# senseBox-MCU_v13.net
KiCad netlist of a schematic drawn in EAGLE
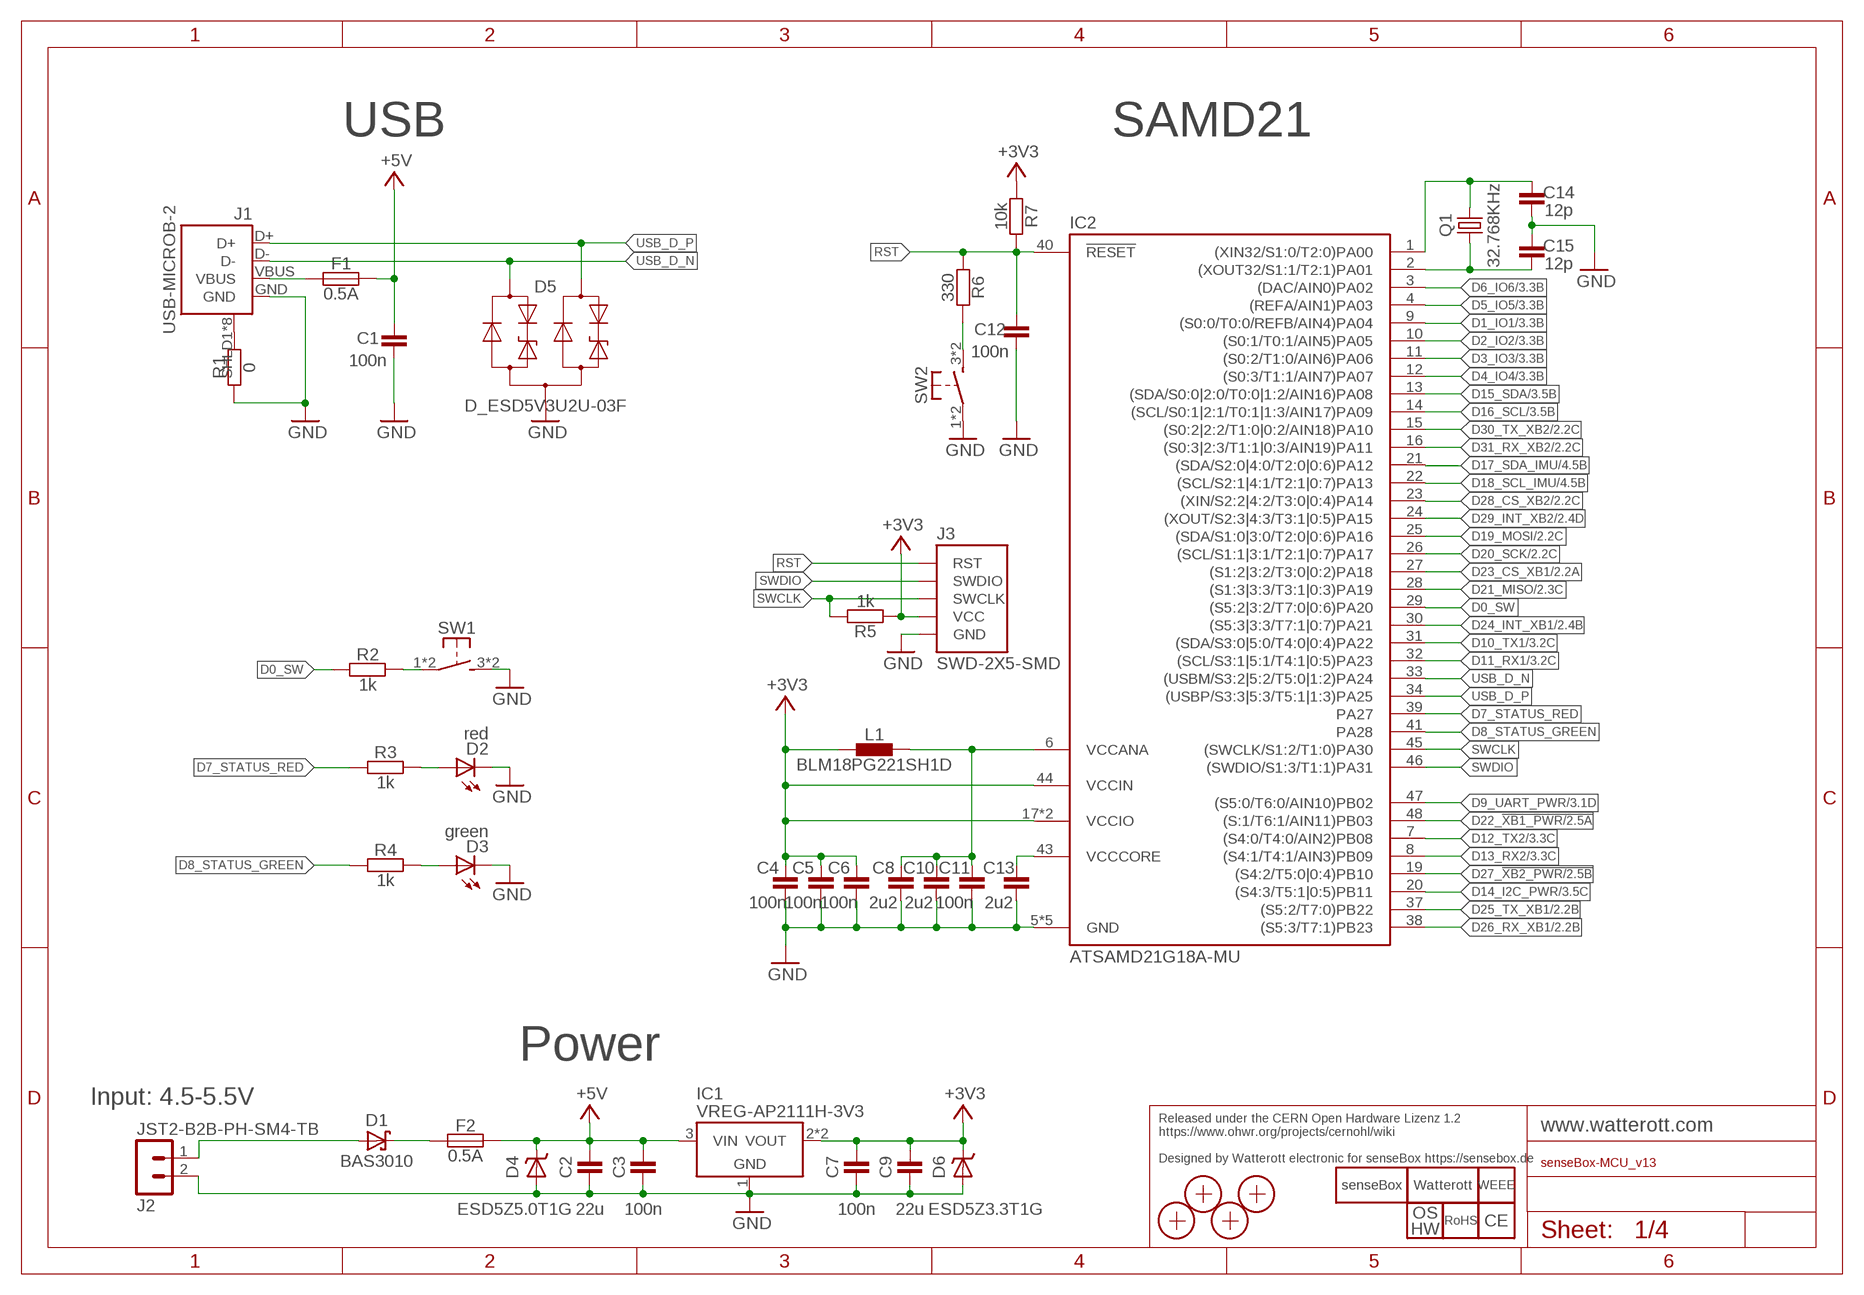
[diagram p0: schematic, sheet 1]
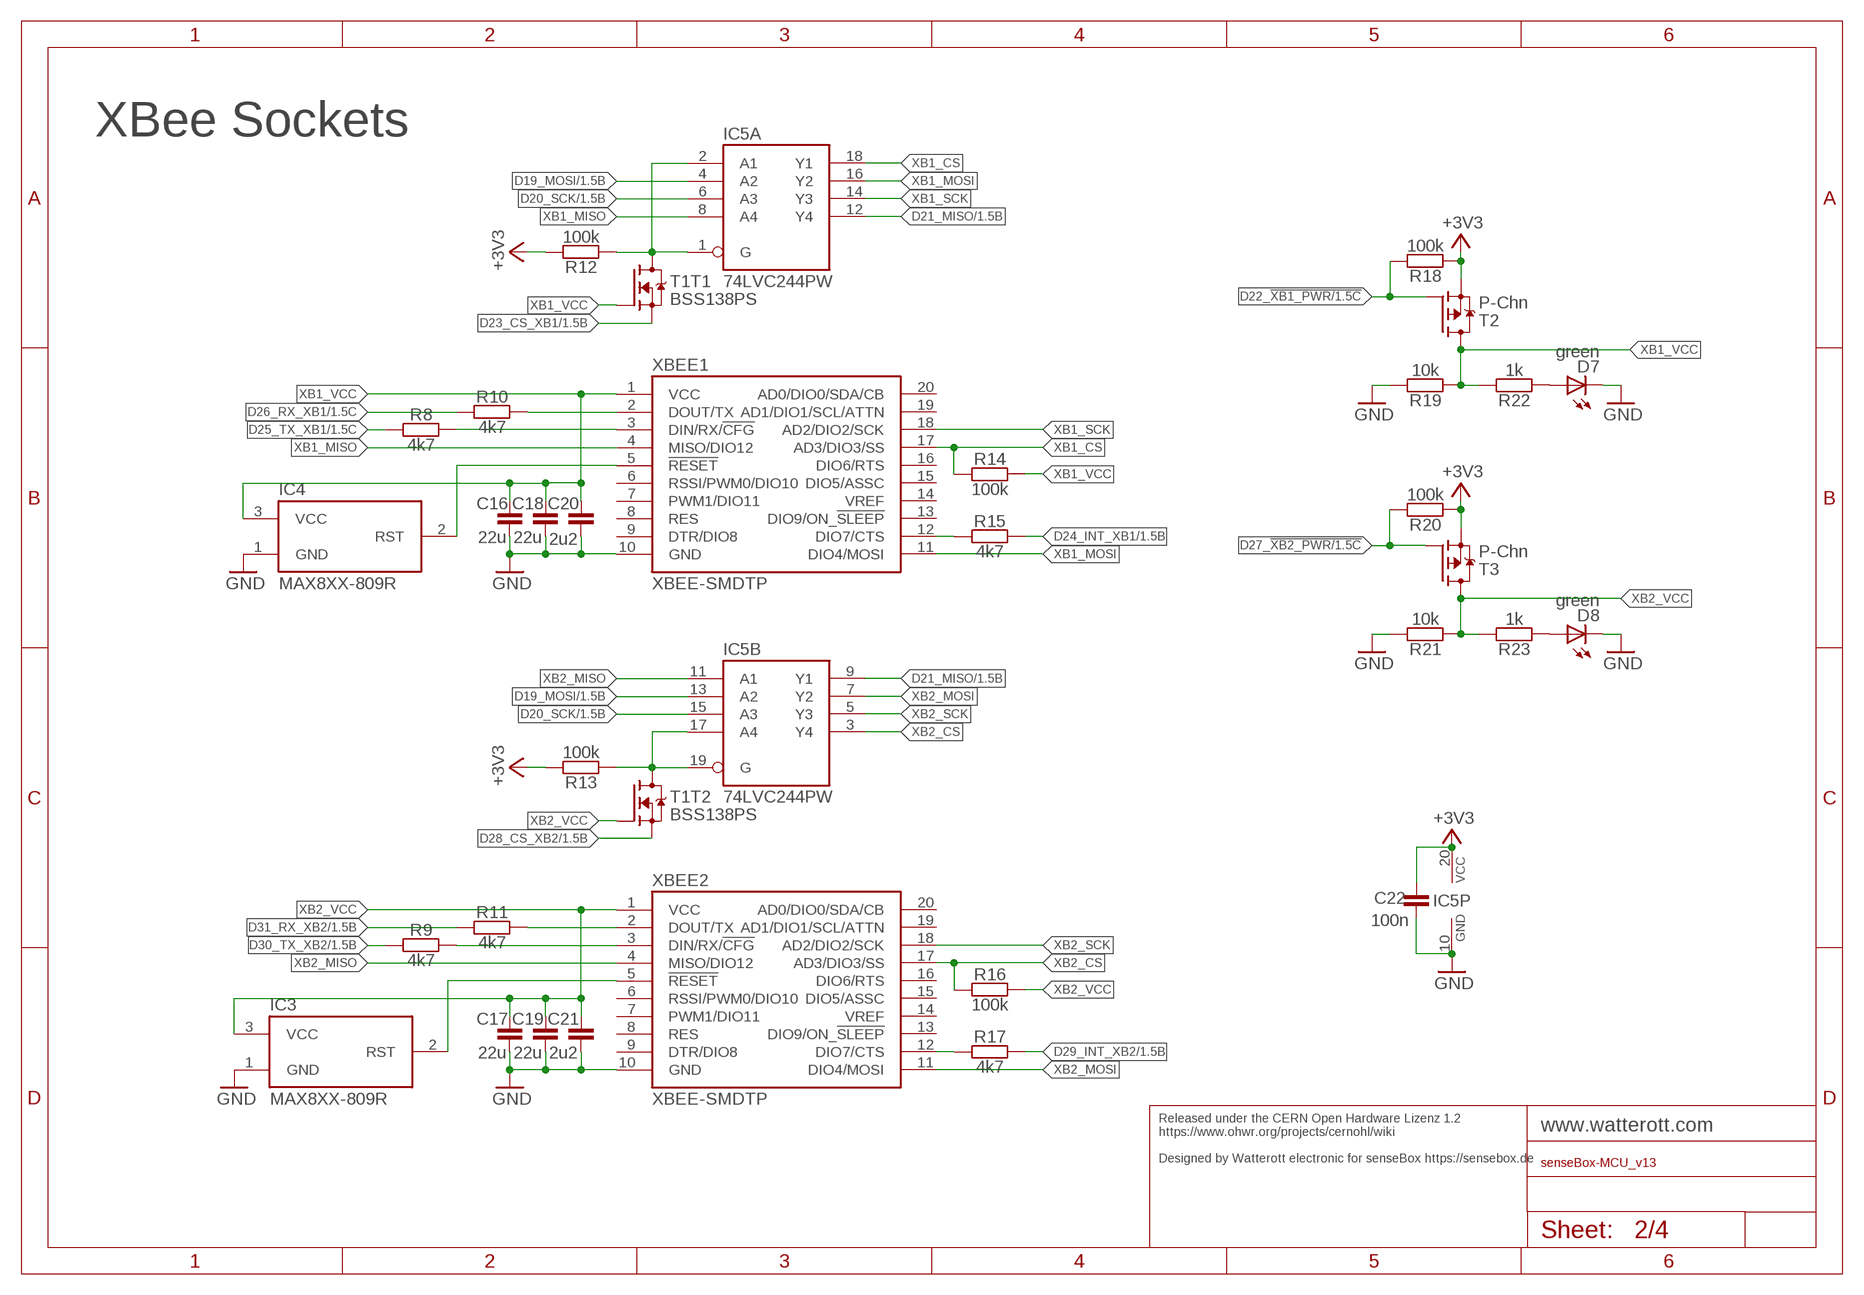
[diagram p1: schematic, sheet 2]
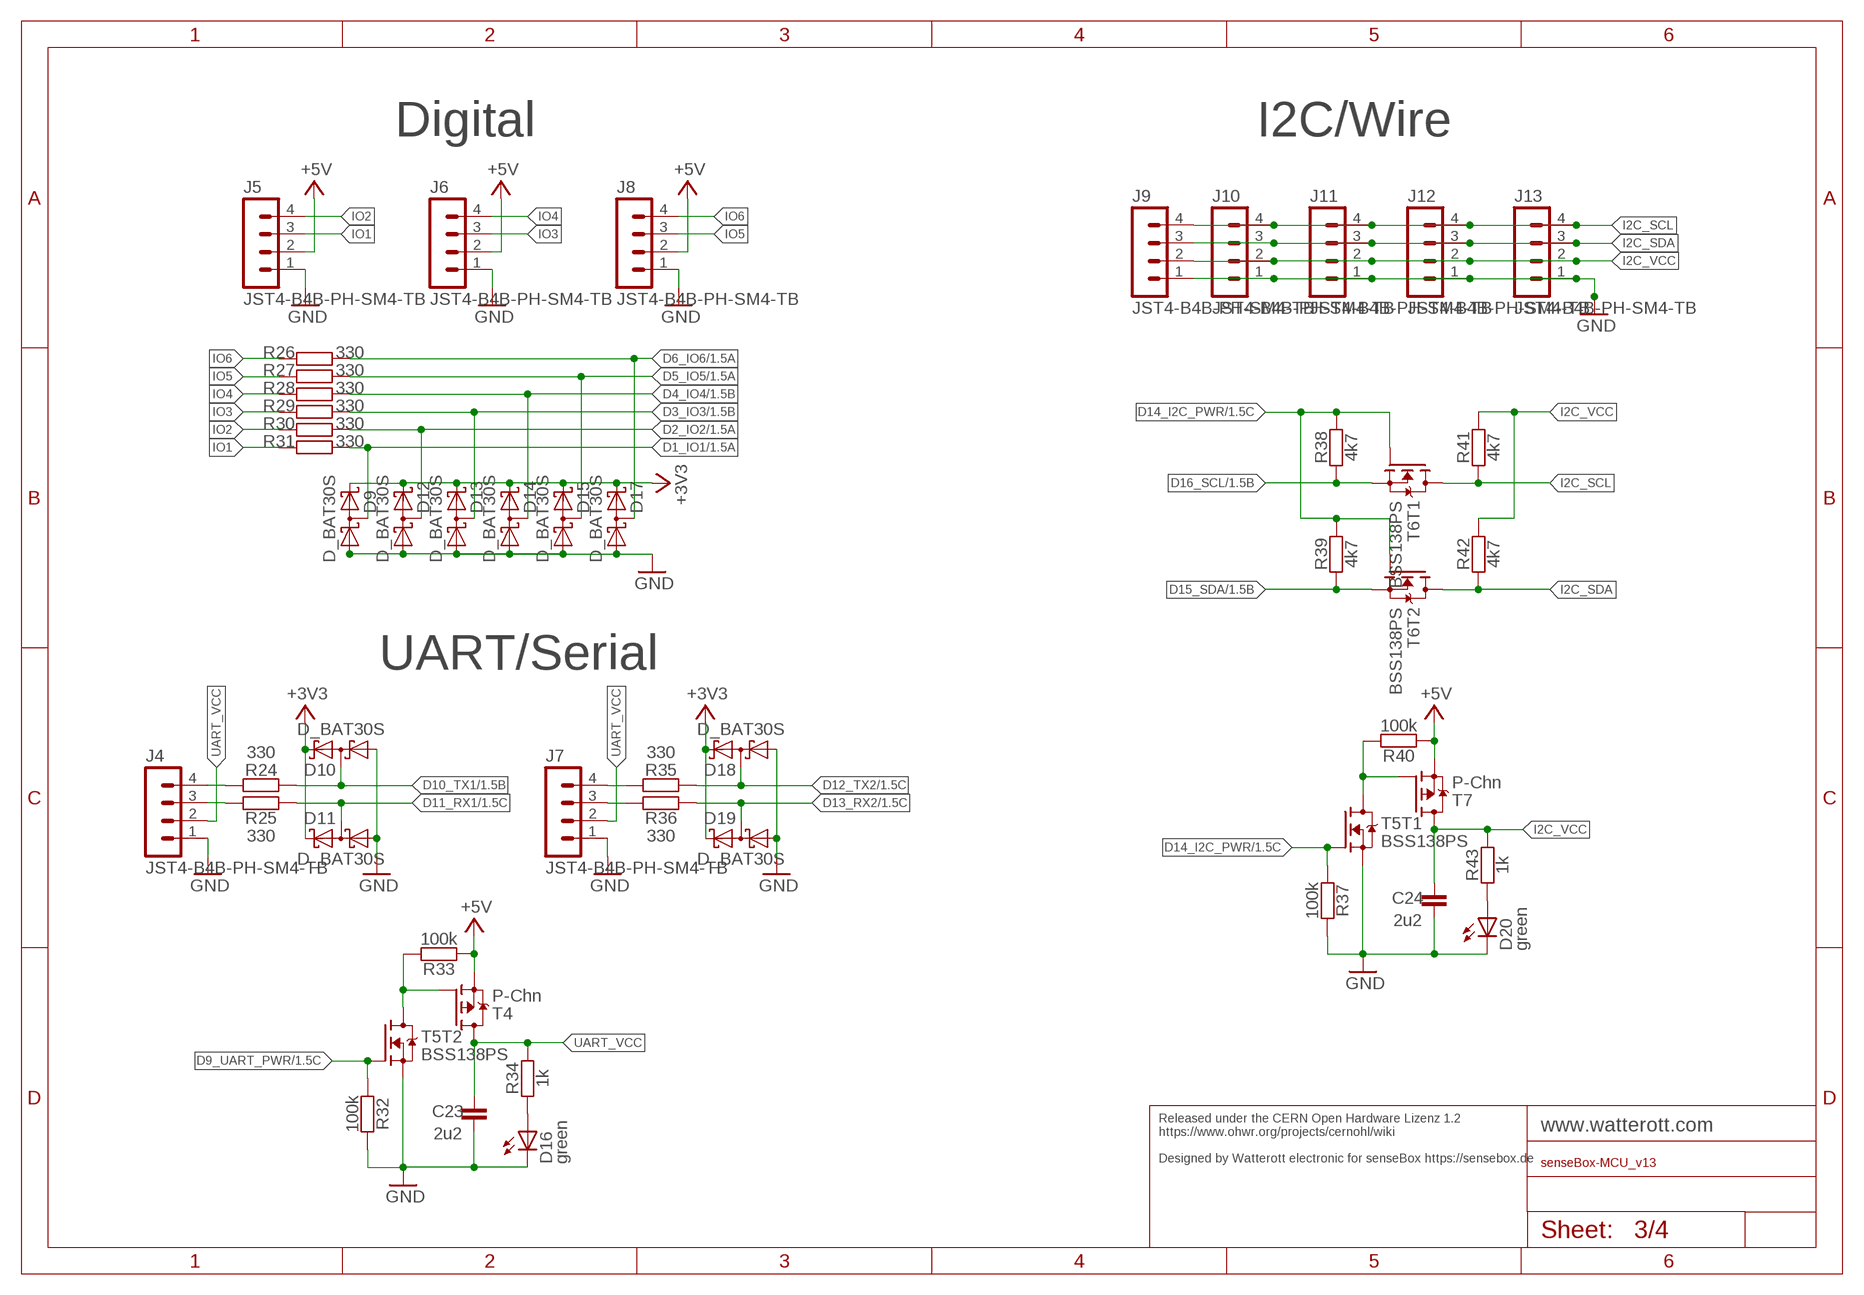
[diagram p2: schematic, sheet 3]
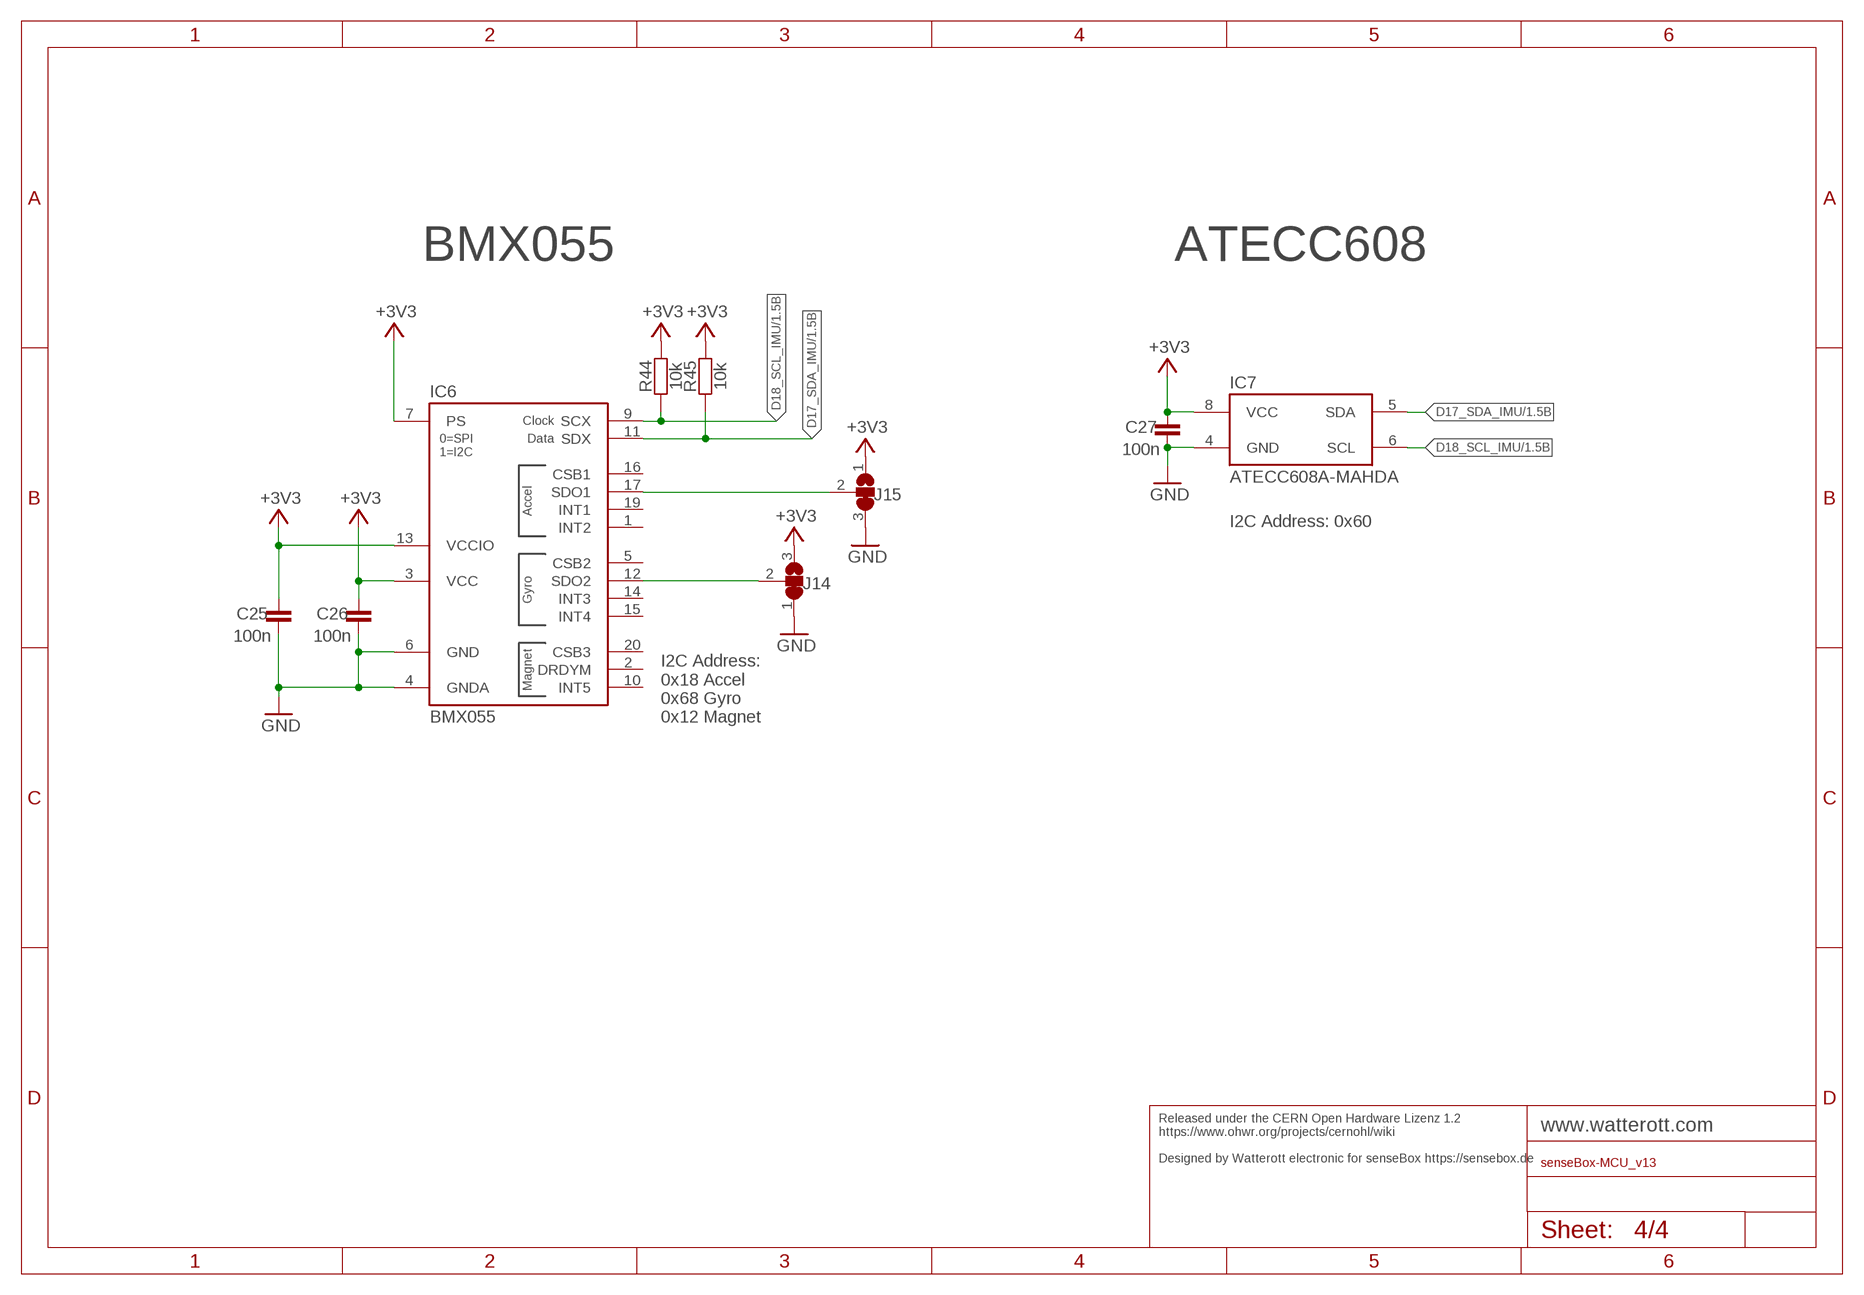
[diagram p3: schematic, sheet 4]

(export (version "E")
  (design (tool "Eeschema 10.0.6"))
  (components
    (comp (ref "C25")
      (value "100n")
      (footprint "eagle-import:C0402")
      (libsource (lib "eagle-import") (part "CAPACITOR-0402"))
    )
    (comp (ref "C26")
      (value "100n")
      (footprint "eagle-import:C0402")
      (libsource (lib "eagle-import") (part "CAPACITOR-0402"))
    )
    (comp (ref "C27")
      (value "100n")
      (footprint "eagle-import:C0402")
      (libsource (lib "eagle-import") (part "CAPACITOR-0402"))
    )
    (comp (ref "IC6")
      (value "BMX055")
      (footprint "eagle-import:BMX055")
      (libsource (lib "eagle-import") (part "BMX055"))
    )
    (comp (ref "IC7")
      (value "ATECC608A-MAHDA")
      (footprint "eagle-import:UDFN8")
      (libsource (lib "eagle-import") (part "ATECC608A-MAHDA"))
    )
    (comp (ref "J14")
      (value "JUMPER3-0402")
      (footprint "eagle-import:JUMPER3-0402")
      (libsource (lib "eagle-import") (part "JUMPER3-0402"))
    )
    (comp (ref "J15")
      (value "JUMPER3-0402")
      (footprint "eagle-import:JUMPER3-0402")
      (libsource (lib "eagle-import") (part "JUMPER3-0402"))
    )
    (comp (ref "R44")
      (value "10k")
      (footprint "eagle-import:C0402")
      (libsource (lib "eagle-import") (part "RESISTOR-0402"))
    )
    (comp (ref "R45")
      (value "10k")
      (footprint "eagle-import:C0402")
      (libsource (lib "eagle-import") (part "RESISTOR-0402"))
    )
    (comp (ref "C23")
      (value "2u2")
      (footprint "eagle-import:C0402")
      (libsource (lib "eagle-import") (part "CAPACITOR-0402"))
    )
    (comp (ref "C24")
      (value "2u2")
      (footprint "eagle-import:C0402")
      (libsource (lib "eagle-import") (part "CAPACITOR-0402"))
    )
    (comp (ref "D9")
      (value "D_BAT30S")
      (footprint "eagle-import:SOT323")
      (libsource (lib "eagle-import") (part "D_BAT30S"))
    )
    (comp (ref "D10")
      (value "D_BAT30S")
      (footprint "eagle-import:SOT323")
      (libsource (lib "eagle-import") (part "D_BAT30S"))
    )
    (comp (ref "D11")
      (value "D_BAT30S")
      (footprint "eagle-import:SOT323")
      (libsource (lib "eagle-import") (part "D_BAT30S"))
    )
    (comp (ref "D12")
      (value "D_BAT30S")
      (footprint "eagle-import:SOT323")
      (libsource (lib "eagle-import") (part "D_BAT30S"))
    )
    (comp (ref "D13")
      (value "D_BAT30S")
      (footprint "eagle-import:SOT323")
      (libsource (lib "eagle-import") (part "D_BAT30S"))
    )
    (comp (ref "D14")
      (value "D_BAT30S")
      (footprint "eagle-import:SOT323")
      (libsource (lib "eagle-import") (part "D_BAT30S"))
    )
    (comp (ref "D15")
      (value "D_BAT30S")
      (footprint "eagle-import:SOT323")
      (libsource (lib "eagle-import") (part "D_BAT30S"))
    )
    (comp (ref "D16")
      (value "green")
      (footprint "eagle-import:C0603")
      (libsource (lib "eagle-import") (part "LED-0603"))
    )
    (comp (ref "D17")
      (value "D_BAT30S")
      (footprint "eagle-import:SOT323")
      (libsource (lib "eagle-import") (part "D_BAT30S"))
    )
    (comp (ref "D18")
      (value "D_BAT30S")
      (footprint "eagle-import:SOT323")
      (libsource (lib "eagle-import") (part "D_BAT30S"))
    )
    (comp (ref "D19")
      (value "D_BAT30S")
      (footprint "eagle-import:SOT323")
      (libsource (lib "eagle-import") (part "D_BAT30S"))
    )
    (comp (ref "D20")
      (value "green")
      (footprint "eagle-import:C0603")
      (libsource (lib "eagle-import") (part "LED-0603"))
    )
    (comp (ref "J4")
      (value "JST4-B4B-PH-SM4-TB")
      (footprint "eagle-import:JST_B4B-PH-SM4-TB")
      (libsource (lib "eagle-import") (part "JST4-B4B-PH-SM4-TB"))
    )
    (comp (ref "J5")
      (value "JST4-B4B-PH-SM4-TB")
      (footprint "eagle-import:JST_B4B-PH-SM4-TB")
      (libsource (lib "eagle-import") (part "JST4-B4B-PH-SM4-TB"))
    )
    (comp (ref "J6")
      (value "JST4-B4B-PH-SM4-TB")
      (footprint "eagle-import:JST_B4B-PH-SM4-TB")
      (libsource (lib "eagle-import") (part "JST4-B4B-PH-SM4-TB"))
    )
    (comp (ref "J7")
      (value "JST4-B4B-PH-SM4-TB")
      (footprint "eagle-import:JST_B4B-PH-SM4-TB")
      (libsource (lib "eagle-import") (part "JST4-B4B-PH-SM4-TB"))
    )
    (comp (ref "J8")
      (value "JST4-B4B-PH-SM4-TB")
      (footprint "eagle-import:JST_B4B-PH-SM4-TB")
      (libsource (lib "eagle-import") (part "JST4-B4B-PH-SM4-TB"))
    )
    (comp (ref "J9")
      (value "JST4-B4B-PH-SM4-TB")
      (footprint "eagle-import:JST_B4B-PH-SM4-TB")
      (libsource (lib "eagle-import") (part "JST4-B4B-PH-SM4-TB"))
    )
    (comp (ref "J10")
      (value "JST4-B4B-PH-SM4-TB")
      (footprint "eagle-import:JST_B4B-PH-SM4-TB")
      (libsource (lib "eagle-import") (part "JST4-B4B-PH-SM4-TB"))
    )
    (comp (ref "J11")
      (value "JST4-B4B-PH-SM4-TB")
      (footprint "eagle-import:JST_B4B-PH-SM4-TB")
      (libsource (lib "eagle-import") (part "JST4-B4B-PH-SM4-TB"))
    )
    (comp (ref "J12")
      (value "JST4-B4B-PH-SM4-TB")
      (footprint "eagle-import:JST_B4B-PH-SM4-TB")
      (libsource (lib "eagle-import") (part "JST4-B4B-PH-SM4-TB"))
    )
    (comp (ref "J13")
      (value "JST4-B4B-PH-SM4-TB")
      (footprint "eagle-import:JST_B4B-PH-SM4-TB")
      (libsource (lib "eagle-import") (part "JST4-B4B-PH-SM4-TB"))
    )
    (comp (ref "R24")
      (value "330")
      (footprint "eagle-import:C0402")
      (libsource (lib "eagle-import") (part "RESISTOR-0402"))
    )
    (comp (ref "R25")
      (value "330")
      (footprint "eagle-import:C0402")
      (libsource (lib "eagle-import") (part "RESISTOR-0402"))
    )
    (comp (ref "R26")
      (value "330")
      (footprint "eagle-import:C0402")
      (libsource (lib "eagle-import") (part "RESISTOR-0402"))
    )
    (comp (ref "R27")
      (value "330")
      (footprint "eagle-import:C0402")
      (libsource (lib "eagle-import") (part "RESISTOR-0402"))
    )
    (comp (ref "R28")
      (value "330")
      (footprint "eagle-import:C0402")
      (libsource (lib "eagle-import") (part "RESISTOR-0402"))
    )
    (comp (ref "R29")
      (value "330")
      (footprint "eagle-import:C0402")
      (libsource (lib "eagle-import") (part "RESISTOR-0402"))
    )
    (comp (ref "R30")
      (value "330")
      (footprint "eagle-import:C0402")
      (libsource (lib "eagle-import") (part "RESISTOR-0402"))
    )
    (comp (ref "R31")
      (value "330")
      (footprint "eagle-import:C0402")
      (libsource (lib "eagle-import") (part "RESISTOR-0402"))
    )
    (comp (ref "R32")
      (value "100k")
      (footprint "eagle-import:C0402")
      (libsource (lib "eagle-import") (part "RESISTOR-0402"))
    )
    (comp (ref "R33")
      (value "100k")
      (footprint "eagle-import:C0402")
      (libsource (lib "eagle-import") (part "RESISTOR-0402"))
    )
    (comp (ref "R34")
      (value "1k")
      (footprint "eagle-import:C0402")
      (libsource (lib "eagle-import") (part "RESISTOR-0402"))
    )
    (comp (ref "R35")
      (value "330")
      (footprint "eagle-import:C0402")
      (libsource (lib "eagle-import") (part "RESISTOR-0402"))
    )
    (comp (ref "R36")
      (value "330")
      (footprint "eagle-import:C0402")
      (libsource (lib "eagle-import") (part "RESISTOR-0402"))
    )
    (comp (ref "R37")
      (value "100k")
      (footprint "eagle-import:C0402")
      (libsource (lib "eagle-import") (part "RESISTOR-0402"))
    )
    (comp (ref "R38")
      (value "4k7")
      (footprint "eagle-import:C0402")
      (libsource (lib "eagle-import") (part "RESISTOR-0402"))
    )
    (comp (ref "R39")
      (value "4k7")
      (footprint "eagle-import:C0402")
      (libsource (lib "eagle-import") (part "RESISTOR-0402"))
    )
    (comp (ref "R40")
      (value "100k")
      (footprint "eagle-import:C0402")
      (libsource (lib "eagle-import") (part "RESISTOR-0402"))
    )
    (comp (ref "R41")
      (value "4k7")
      (footprint "eagle-import:C0402")
      (libsource (lib "eagle-import") (part "RESISTOR-0402"))
    )
    (comp (ref "R42")
      (value "4k7")
      (footprint "eagle-import:C0402")
      (libsource (lib "eagle-import") (part "RESISTOR-0402"))
    )
    (comp (ref "R43")
      (value "1k")
      (footprint "eagle-import:C0402")
      (libsource (lib "eagle-import") (part "RESISTOR-0402"))
    )
    (comp (ref "T4")
      (value "P-Chn")
      (footprint "eagle-import:SOT23")
      (libsource (lib "eagle-import") (part "MOSFET-P-SOT23"))
    )
    (comp (ref "T5")
      (value "BSS138PS")
      (footprint "eagle-import:SOT363")
      (libsource (lib "eagle-import") (part "BSS138PS"))
    )
    (comp (ref "T6")
      (value "BSS138PS")
      (footprint "eagle-import:SOT363")
      (libsource (lib "eagle-import") (part "BSS138PS"))
    )
    (comp (ref "T7")
      (value "P-Chn")
      (footprint "eagle-import:SOT23")
      (libsource (lib "eagle-import") (part "MOSFET-P-SOT23"))
    )
    (comp (ref "C1")
      (value "100n")
      (footprint "eagle-import:C0402")
      (libsource (lib "eagle-import") (part "CAPACITOR-0402"))
    )
    (comp (ref "C2")
      (value "22u")
      (footprint "eagle-import:C0805")
      (libsource (lib "eagle-import") (part "CAPACITOR-0805"))
    )
    (comp (ref "C3")
      (value "100n")
      (footprint "eagle-import:C0402")
      (libsource (lib "eagle-import") (part "CAPACITOR-0402"))
    )
    (comp (ref "C4")
      (value "100n")
      (footprint "eagle-import:C0402")
      (libsource (lib "eagle-import") (part "CAPACITOR-0402"))
    )
    (comp (ref "C5")
      (value "100n")
      (footprint "eagle-import:C0402")
      (libsource (lib "eagle-import") (part "CAPACITOR-0402"))
    )
    (comp (ref "C6")
      (value "100n")
      (footprint "eagle-import:C0402")
      (libsource (lib "eagle-import") (part "CAPACITOR-0402"))
    )
    (comp (ref "C7")
      (value "100n")
      (footprint "eagle-import:C0402")
      (libsource (lib "eagle-import") (part "CAPACITOR-0402"))
    )
    (comp (ref "C8")
      (value "2u2")
      (footprint "eagle-import:C0402")
      (libsource (lib "eagle-import") (part "CAPACITOR-0402"))
    )
    (comp (ref "C9")
      (value "22u")
      (footprint "eagle-import:C0805")
      (libsource (lib "eagle-import") (part "CAPACITOR-0805"))
    )
    (comp (ref "C10")
      (value "2u2")
      (footprint "eagle-import:C0402")
      (libsource (lib "eagle-import") (part "CAPACITOR-0402"))
    )
    (comp (ref "C11")
      (value "100n")
      (footprint "eagle-import:C0402")
      (libsource (lib "eagle-import") (part "CAPACITOR-0402"))
    )
    (comp (ref "C12")
      (value "100n")
      (footprint "eagle-import:C0402")
      (libsource (lib "eagle-import") (part "CAPACITOR-0402"))
    )
    (comp (ref "C13")
      (value "2u2")
      (footprint "eagle-import:C0402")
      (libsource (lib "eagle-import") (part "CAPACITOR-0402"))
    )
    (comp (ref "C14")
      (value "12p")
      (footprint "eagle-import:C0402")
      (libsource (lib "eagle-import") (part "CAPACITOR-0402"))
    )
    (comp (ref "C15")
      (value "12p")
      (footprint "eagle-import:C0402")
      (libsource (lib "eagle-import") (part "CAPACITOR-0402"))
    )
    (comp (ref "D1")
      (value "BAS3010")
      (footprint "eagle-import:SOD323")
      (libsource (lib "eagle-import") (part "D_SCHOTTKY-SOD323"))
    )
    (comp (ref "D2")
      (value "red")
      (footprint "eagle-import:C0603")
      (libsource (lib "eagle-import") (part "LED-0603"))
    )
    (comp (ref "D3")
      (value "green")
      (footprint "eagle-import:C0603")
      (libsource (lib "eagle-import") (part "LED-0603"))
    )
    (comp (ref "D4")
      (value "ESD5Z5.0T1G")
      (footprint "eagle-import:SOD523")
      (libsource (lib "eagle-import") (part "D_TVS-SOD523"))
    )
    (comp (ref "D5")
      (value "D_ESD5V3U2U-03F")
      (footprint "eagle-import:SOT723")
      (libsource (lib "eagle-import") (part "D_ESD5V3U2U-03F"))
    )
    (comp (ref "D6")
      (value "ESD5Z3.3T1G")
      (footprint "eagle-import:SOD523")
      (libsource (lib "eagle-import") (part "D_TVS-SOD523"))
    )
    (comp (ref "F1")
      (value "0.5A")
      (footprint "eagle-import:C0805")
      (libsource (lib "eagle-import") (part "FUSE-0805"))
    )
    (comp (ref "F2")
      (value "0.5A")
      (footprint "eagle-import:C0805")
      (libsource (lib "eagle-import") (part "FUSE-0805"))
    )
    (comp (ref "IC1")
      (value "VREG-AP2111H-3V3")
      (footprint "eagle-import:SOT223")
      (libsource (lib "eagle-import") (part "VREG-TS1117CW-3V3"))
    )
    (comp (ref "IC2")
      (value "ATSAMD21G18A-MU")
      (footprint "eagle-import:QFN48-PAD")
      (libsource (lib "eagle-import") (part "ATSAMD21G18A-MU"))
    )
    (comp (ref "J1")
      (value "USB-MICROB-2")
      (footprint "eagle-import:USB-MICROB-10118194")
      (libsource (lib "eagle-import") (part "USB-MICROB-2"))
    )
    (comp (ref "J2")
      (value "JST2-B2B-PH-SM4-TB")
      (footprint "eagle-import:JST_B2B-PH-SM4-TB")
      (libsource (lib "eagle-import") (part "JST2-B2B-PH-SM4-TB"))
    )
    (comp (ref "J3")
      (value "SWD-2X5-SMD")
      (footprint "eagle-import:SWD-2X5_SMD")
      (libsource (lib "eagle-import") (part "SWD-2X5-SMD"))
    )
    (comp (ref "L1")
      (value "BLM18PG221SH1D")
      (footprint "eagle-import:C0603")
      (libsource (lib "eagle-import") (part "INDUCTOR-0603"))
    )
    (comp (ref "LOGO1")
      (value "LOGO_SENSEBOX-12")
      (footprint "eagle-import:SB_12MM")
      (libsource (lib "eagle-import") (part "LOGO_SENSEBOX-12"))
    )
    (comp (ref "LOGO3")
      (value "OSHW_LOGOX0070")
      (footprint "eagle-import:OSHW_3MM")
      (libsource (lib "eagle-import") (part "LOGO_OSHW-3"))
    )
    (comp (ref "LOGO4")
      (value "LOGO_SPARK-4")
      (footprint "eagle-import:SPARK_4MM")
      (libsource (lib "eagle-import") (part "LOGO_SPARK-4"))
    )
    (comp (ref "LOGO5")
      (value "LOGO_ROHS-4")
      (footprint "eagle-import:ROHS_4MM")
      (libsource (lib "eagle-import") (part "LOGO_ROHS-4"))
    )
    (comp (ref "LOGO6")
      (value "LOGO_WEEE-4")
      (footprint "eagle-import:WEEE_4MM")
      (libsource (lib "eagle-import") (part "LOGO_WEEE-4"))
    )
    (comp (ref "LOGO7")
      (value "LOGO_CE-4")
      (footprint "eagle-import:CE_4MM")
      (libsource (lib "eagle-import") (part "LOGO_CE-4"))
    )
    (comp (ref "Q1")
      (value "32.768KHz")
      (footprint "eagle-import:CRYSTAL_ZM315")
      (libsource (lib "eagle-import") (part "CRYSTAL-ZM315"))
    )
    (comp (ref "R1")
      (value "0")
      (footprint "eagle-import:C0402")
      (libsource (lib "eagle-import") (part "RESISTOR-0402"))
    )
    (comp (ref "R2")
      (value "1k")
      (footprint "eagle-import:C0402")
      (libsource (lib "eagle-import") (part "RESISTOR-0402"))
    )
    (comp (ref "R3")
      (value "1k")
      (footprint "eagle-import:C0402")
      (libsource (lib "eagle-import") (part "RESISTOR-0402"))
    )
    (comp (ref "R4")
      (value "1k")
      (footprint "eagle-import:C0402")
      (libsource (lib "eagle-import") (part "RESISTOR-0402"))
    )
    (comp (ref "R5")
      (value "1k")
      (footprint "eagle-import:C0402")
      (libsource (lib "eagle-import") (part "RESISTOR-0402"))
    )
    (comp (ref "R6")
      (value "330")
      (footprint "eagle-import:C0402")
      (libsource (lib "eagle-import") (part "RESISTOR-0402"))
    )
    (comp (ref "R7")
      (value "10k")
      (footprint "eagle-import:C0402")
      (libsource (lib "eagle-import") (part "RESISTOR-0402"))
    )
    (comp (ref "SW1")
      (value "PTS645SH50SMTR92-Grey")
      (footprint "eagle-import:SW6X6_SMD")
      (libsource (lib "eagle-import") (part "SW-TACTILE-6X6_SMD"))
    )
    (comp (ref "SW2")
      (value "PTS645SK50SMTR92-Red")
      (footprint "eagle-import:SW6X6_SMD")
      (libsource (lib "eagle-import") (part "SW-TACTILE-6X6_SMD"))
    )
    (comp (ref "X1")
      (value "PASSER-07")
      (footprint "eagle-import:PASSER_07MM")
      (libsource (lib "eagle-import") (part "PASSER-07"))
    )
    (comp (ref "X2")
      (value "PASSER-07")
      (footprint "eagle-import:PASSER_07MM")
      (libsource (lib "eagle-import") (part "PASSER-07"))
    )
    (comp (ref "X3")
      (value "PASSER-07")
      (footprint "eagle-import:PASSER_07MM")
      (libsource (lib "eagle-import") (part "PASSER-07"))
    )
    (comp (ref "X4")
      (value "PASSER-07")
      (footprint "eagle-import:PASSER_07MM")
      (libsource (lib "eagle-import") (part "PASSER-07"))
    )
    (comp (ref "C16")
      (value "22u")
      (footprint "eagle-import:C0805")
      (libsource (lib "eagle-import") (part "CAPACITOR-0805"))
    )
    (comp (ref "C17")
      (value "22u")
      (footprint "eagle-import:C0805")
      (libsource (lib "eagle-import") (part "CAPACITOR-0805"))
    )
    (comp (ref "C18")
      (value "22u")
      (footprint "eagle-import:C0805")
      (libsource (lib "eagle-import") (part "CAPACITOR-0805"))
    )
    (comp (ref "C19")
      (value "22u")
      (footprint "eagle-import:C0805")
      (libsource (lib "eagle-import") (part "CAPACITOR-0805"))
    )
    (comp (ref "C20")
      (value "2u2")
      (footprint "eagle-import:C0402")
      (libsource (lib "eagle-import") (part "CAPACITOR-0402"))
    )
    (comp (ref "C21")
      (value "2u2")
      (footprint "eagle-import:C0402")
      (libsource (lib "eagle-import") (part "CAPACITOR-0402"))
    )
    (comp (ref "C22")
      (value "100n")
      (footprint "eagle-import:C0402")
      (libsource (lib "eagle-import") (part "CAPACITOR-0402"))
    )
    (comp (ref "D7")
      (value "green")
      (footprint "eagle-import:C0603")
      (libsource (lib "eagle-import") (part "LED-0603"))
    )
    (comp (ref "D8")
      (value "green")
      (footprint "eagle-import:C0603")
      (libsource (lib "eagle-import") (part "LED-0603"))
    )
    (comp (ref "IC3")
      (value "MAX8XX-809R")
      (footprint "eagle-import:SOT23")
      (libsource (lib "eagle-import") (part "MAX8XX-809R"))
    )
    (comp (ref "IC4")
      (value "MAX8XX-809R")
      (footprint "eagle-import:SOT23")
      (libsource (lib "eagle-import") (part "MAX8XX-809R"))
    )
    (comp (ref "IC5")
      (value "74LVC244PW")
      (footprint "eagle-import:TSSOP20")
      (libsource (lib "eagle-import") (part "74244PWLVC"))
    )
    (comp (ref "R8")
      (value "4k7")
      (footprint "eagle-import:C0402")
      (libsource (lib "eagle-import") (part "RESISTOR-0402"))
    )
    (comp (ref "R9")
      (value "4k7")
      (footprint "eagle-import:C0402")
      (libsource (lib "eagle-import") (part "RESISTOR-0402"))
    )
    (comp (ref "R10")
      (value "4k7")
      (footprint "eagle-import:C0402")
      (libsource (lib "eagle-import") (part "RESISTOR-0402"))
    )
    (comp (ref "R11")
      (value "4k7")
      (footprint "eagle-import:C0402")
      (libsource (lib "eagle-import") (part "RESISTOR-0402"))
    )
    (comp (ref "R12")
      (value "100k")
      (footprint "eagle-import:C0402")
      (libsource (lib "eagle-import") (part "RESISTOR-0402"))
    )
    (comp (ref "R13")
      (value "100k")
      (footprint "eagle-import:C0402")
      (libsource (lib "eagle-import") (part "RESISTOR-0402"))
    )
    (comp (ref "R14")
      (value "100k")
      (footprint "eagle-import:C0402")
      (libsource (lib "eagle-import") (part "RESISTOR-0402"))
    )
    (comp (ref "R15")
      (value "4k7")
      (footprint "eagle-import:C0402")
      (libsource (lib "eagle-import") (part "RESISTOR-0402"))
    )
    (comp (ref "R16")
      (value "100k")
      (footprint "eagle-import:C0402")
      (libsource (lib "eagle-import") (part "RESISTOR-0402"))
    )
    (comp (ref "R17")
      (value "4k7")
      (footprint "eagle-import:C0402")
      (libsource (lib "eagle-import") (part "RESISTOR-0402"))
    )
    (comp (ref "R18")
      (value "100k")
      (footprint "eagle-import:C0402")
      (libsource (lib "eagle-import") (part "RESISTOR-0402"))
    )
    (comp (ref "R19")
      (value "10k")
      (footprint "eagle-import:C0402")
      (libsource (lib "eagle-import") (part "RESISTOR-0402"))
    )
    (comp (ref "R20")
      (value "100k")
      (footprint "eagle-import:C0402")
      (libsource (lib "eagle-import") (part "RESISTOR-0402"))
    )
    (comp (ref "R21")
      (value "10k")
      (footprint "eagle-import:C0402")
      (libsource (lib "eagle-import") (part "RESISTOR-0402"))
    )
    (comp (ref "R22")
      (value "1k")
      (footprint "eagle-import:C0402")
      (libsource (lib "eagle-import") (part "RESISTOR-0402"))
    )
    (comp (ref "R23")
      (value "1k")
      (footprint "eagle-import:C0402")
      (libsource (lib "eagle-import") (part "RESISTOR-0402"))
    )
    (comp (ref "T1")
      (value "BSS138PS")
      (footprint "eagle-import:SOT363")
      (libsource (lib "eagle-import") (part "BSS138PS"))
    )
    (comp (ref "T2")
      (value "P-Chn")
      (footprint "eagle-import:SOT23")
      (libsource (lib "eagle-import") (part "MOSFET-P-SOT23"))
    )
    (comp (ref "T3")
      (value "P-Chn")
      (footprint "eagle-import:SOT23")
      (libsource (lib "eagle-import") (part "MOSFET-P-SOT23"))
    )
    (comp (ref "XBEE1")
      (value "XBEE-SMDTP")
      (footprint "eagle-import:XBEE_SMD_TP")
      (libsource (lib "eagle-import") (part "XBEE-SMDTP"))
    )
    (comp (ref "XBEE2")
      (value "XBEE-SMDTP")
      (footprint "eagle-import:XBEE_SMD_TP")
      (libsource (lib "eagle-import") (part "XBEE-SMDTP"))
    )
  )
  (nets
    (net (code "1") (name "+3V3") (class "Default")
      (node (ref "C22") (pin "2") (pinfunction "2_2") (pintype "passive"))
      (node (ref "C25") (pin "2") (pinfunction "2_2") (pintype "passive"))
      (node (ref "C26") (pin "2") (pinfunction "2_2") (pintype "passive"))
      (node (ref "C27") (pin "2") (pinfunction "2_2") (pintype "passive"))
      (node (ref "C4") (pin "2") (pinfunction "2_2") (pintype "passive"))
      (node (ref "C5") (pin "2") (pinfunction "2_2") (pintype "passive"))
      (node (ref "C6") (pin "2") (pinfunction "2_2") (pintype "passive"))
      (node (ref "C7") (pin "2") (pinfunction "2_2") (pintype "passive"))
      (node (ref "C9") (pin "2") (pinfunction "2_2") (pintype "passive"))
      (node (ref "D10") (pin "2") (pinfunction "C_2") (pintype "passive"))
      (node (ref "D11") (pin "2") (pinfunction "C_2") (pintype "passive"))
      (node (ref "D12") (pin "2") (pinfunction "C_2") (pintype "passive"))
      (node (ref "D13") (pin "2") (pinfunction "C_2") (pintype "passive"))
      (node (ref "D14") (pin "2") (pinfunction "C_2") (pintype "passive"))
      (node (ref "D15") (pin "2") (pinfunction "C_2") (pintype "passive"))
      (node (ref "D17") (pin "2") (pinfunction "C_2") (pintype "passive"))
      (node (ref "D18") (pin "2") (pinfunction "C_2") (pintype "passive"))
      (node (ref "D19") (pin "2") (pinfunction "C_2") (pintype "passive"))
      (node (ref "D6") (pin "C") (pinfunction "C_C") (pintype "passive"))
      (node (ref "D9") (pin "2") (pinfunction "C_2") (pintype "passive"))
      (node (ref "IC1") (pin "2") (pinfunction "VOUT_2") (pintype "power_in"))
      (node (ref "IC1") (pin "4") (pinfunction "VOUT_4") (pintype "power_in"))
      (node (ref "IC2") (pin "17") (pinfunction "VCCIO_17") (pintype "power_in"))
      (node (ref "IC2") (pin "36") (pinfunction "VCCIO_36") (pintype "power_in"))
      (node (ref "IC2") (pin "44") (pinfunction "VCCIN_44") (pintype "power_in"))
      (node (ref "IC5") (pin "20") (pinfunction "VCC_20") (pintype "power_in"))
      (node (ref "IC6") (pin "13") (pinfunction "VCCIO_13") (pintype "power_in"))
      (node (ref "IC6") (pin "3") (pinfunction "VCC_3") (pintype "power_in"))
      (node (ref "IC6") (pin "7") (pinfunction "PS_7") (pintype "input"))
      (node (ref "IC7") (pin "8") (pinfunction "VCC_8") (pintype "power_in"))
      (node (ref "J14") (pin "3") (pinfunction "3_3") (pintype "passive"))
      (node (ref "J15") (pin "1") (pinfunction "1_1") (pintype "passive"))
      (node (ref "J3") (pin "VCC") (pinfunction "VCC_VCC") (pintype "power_in"))
      (node (ref "L1") (pin "1") (pinfunction "1_1") (pintype "passive"))
      (node (ref "R12") (pin "2") (pinfunction "2_2") (pintype "passive"))
      (node (ref "R13") (pin "2") (pinfunction "2_2") (pintype "passive"))
      (node (ref "R18") (pin "1") (pinfunction "1_1") (pintype "passive"))
      (node (ref "R20") (pin "1") (pinfunction "1_1") (pintype "passive"))
      (node (ref "R44") (pin "2") (pinfunction "2_2") (pintype "passive"))
      (node (ref "R45") (pin "2") (pinfunction "2_2") (pintype "passive"))
      (node (ref "R5") (pin "1") (pinfunction "1_1") (pintype "passive"))
      (node (ref "R7") (pin "1") (pinfunction "1_1") (pintype "passive"))
      (node (ref "T2") (pin "2") (pinfunction "S_2") (pintype "passive"))
      (node (ref "T3") (pin "2") (pinfunction "S_2") (pintype "passive"))
    )
    (net (code "2") (name "+5V") (class "Default")
      (node (ref "C1") (pin "2") (pinfunction "2_2") (pintype "passive"))
      (node (ref "C2") (pin "2") (pinfunction "2_2") (pintype "passive"))
      (node (ref "C3") (pin "2") (pinfunction "2_2") (pintype "passive"))
      (node (ref "D4") (pin "C") (pinfunction "C_C") (pintype "passive"))
      (node (ref "F1") (pin "2") (pinfunction "2_2") (pintype "passive"))
      (node (ref "F2") (pin "2") (pinfunction "2_2") (pintype "passive"))
      (node (ref "IC1") (pin "3") (pinfunction "VIN_3") (pintype "power_in"))
      (node (ref "J5") (pin "2") (pinfunction "2_2") (pintype "passive"))
      (node (ref "J6") (pin "2") (pinfunction "2_2") (pintype "passive"))
      (node (ref "J8") (pin "2") (pinfunction "2_2") (pintype "passive"))
      (node (ref "R33") (pin "1") (pinfunction "1_1") (pintype "passive"))
      (node (ref "R40") (pin "1") (pinfunction "1_1") (pintype "passive"))
      (node (ref "T4") (pin "2") (pinfunction "S_2") (pintype "passive"))
      (node (ref "T7") (pin "2") (pinfunction "S_2") (pintype "passive"))
    )
    (net (code "3") (name "D0_SW") (class "Default")
      (node (ref "IC2") (pin "29") (pinfunction "(S5:2|3:2/T7:0|0:6)PA20_29") (pintype "bidirectional"))
      (node (ref "R2") (pin "1") (pinfunction "1_1") (pintype "passive"))
    )
    (net (code "4") (name "D1_IO1") (class "Default")
      (node (ref "D9") (pin "3") (pinfunction "CA_3") (pintype "passive"))
      (node (ref "IC2") (pin "9") (pinfunction "(S0:0/T0:0/REFB/AIN4)PA04_9") (pintype "bidirectional"))
      (node (ref "R31") (pin "1") (pinfunction "1_1") (pintype "passive"))
    )
    (net (code "5") (name "D2_IO2") (class "Default")
      (node (ref "D12") (pin "3") (pinfunction "CA_3") (pintype "passive"))
      (node (ref "IC2") (pin "10") (pinfunction "(S0:1/T0:1/AIN5)PA05_10") (pintype "bidirectional"))
      (node (ref "R30") (pin "1") (pinfunction "1_1") (pintype "passive"))
    )
    (net (code "6") (name "D3_IO3") (class "Default")
      (node (ref "D13") (pin "3") (pinfunction "CA_3") (pintype "passive"))
      (node (ref "IC2") (pin "11") (pinfunction "(S0:2/T1:0/AIN6)PA06_11") (pintype "bidirectional"))
      (node (ref "R29") (pin "1") (pinfunction "1_1") (pintype "passive"))
    )
    (net (code "7") (name "D4_IO4") (class "Default")
      (node (ref "D14") (pin "3") (pinfunction "CA_3") (pintype "passive"))
      (node (ref "IC2") (pin "12") (pinfunction "(S0:3/T1:1/AIN7)PA07_12") (pintype "bidirectional"))
      (node (ref "R28") (pin "1") (pinfunction "1_1") (pintype "passive"))
    )
    (net (code "8") (name "D5_IO5") (class "Default")
      (node (ref "D15") (pin "3") (pinfunction "CA_3") (pintype "passive"))
      (node (ref "IC2") (pin "4") (pinfunction "(REFA/AIN1)PA03_4") (pintype "bidirectional"))
      (node (ref "R27") (pin "1") (pinfunction "1_1") (pintype "passive"))
    )
    (net (code "9") (name "D6_IO6") (class "Default")
      (node (ref "D17") (pin "3") (pinfunction "CA_3") (pintype "passive"))
      (node (ref "IC2") (pin "3") (pinfunction "(DAC/AIN0)PA02_3") (pintype "bidirectional"))
      (node (ref "R26") (pin "1") (pinfunction "1_1") (pintype "passive"))
    )
    (net (code "10") (name "D7_STATUS_RED") (class "Default")
      (node (ref "IC2") (pin "39") (pinfunction "PA27_39") (pintype "bidirectional"))
      (node (ref "R3") (pin "1") (pinfunction "1_1") (pintype "passive"))
    )
    (net (code "11") (name "D8_STATUS_GREEN") (class "Default")
      (node (ref "IC2") (pin "41") (pinfunction "PA28_41") (pintype "bidirectional"))
      (node (ref "R4") (pin "1") (pinfunction "1_1") (pintype "passive"))
    )
    (net (code "12") (name "D9_UART_PWR") (class "Default")
      (node (ref "IC2") (pin "47") (pinfunction "(S5:0/T6:0/AIN10)PB02_47") (pintype "bidirectional"))
      (node (ref "R32") (pin "1") (pinfunction "1_1") (pintype "passive"))
      (node (ref "T5") (pin "5") (pinfunction "G_5") (pintype "passive"))
    )
    (net (code "13") (name "D10_TX1") (class "Default")
      (node (ref "D10") (pin "3") (pinfunction "CA_3") (pintype "passive"))
      (node (ref "IC2") (pin "31") (pinfunction "(SDA/S3:0|5:0/T4:0|0:4)PA22_31") (pintype "bidirectional"))
      (node (ref "R24") (pin "1") (pinfunction "1_1") (pintype "passive"))
    )
    (net (code "14") (name "D11_RX1") (class "Default")
      (node (ref "D11") (pin "3") (pinfunction "CA_3") (pintype "passive"))
      (node (ref "IC2") (pin "32") (pinfunction "(SCL/S3:1|5:1/T4:1|0:5)PA23_32") (pintype "bidirectional"))
      (node (ref "R25") (pin "1") (pinfunction "1_1") (pintype "passive"))
    )
    (net (code "15") (name "D12_TX2") (class "Default")
      (node (ref "D18") (pin "3") (pinfunction "CA_3") (pintype "passive"))
      (node (ref "IC2") (pin "7") (pinfunction "(S4:0/T4:0/AIN2)PB08_7") (pintype "bidirectional"))
      (node (ref "R35") (pin "1") (pinfunction "1_1") (pintype "passive"))
    )
    (net (code "16") (name "D13_RX2") (class "Default")
      (node (ref "D19") (pin "3") (pinfunction "CA_3") (pintype "passive"))
      (node (ref "IC2") (pin "8") (pinfunction "(S4:1/T4:1/AIN3)PB09_8") (pintype "bidirectional"))
      (node (ref "R36") (pin "1") (pinfunction "1_1") (pintype "passive"))
    )
    (net (code "17") (name "D14_I2C_PWR") (class "Default")
      (node (ref "IC2") (pin "20") (pinfunction "(S4:3/T5:1|0:5)PB11_20") (pintype "bidirectional"))
      (node (ref "R37") (pin "1") (pinfunction "1_1") (pintype "passive"))
      (node (ref "R38") (pin "2") (pinfunction "2_2") (pintype "passive"))
      (node (ref "R39") (pin "2") (pinfunction "2_2") (pintype "passive"))
      (node (ref "T5") (pin "2") (pinfunction "G_2") (pintype "passive"))
      (node (ref "T6") (pin "2") (pinfunction "G_2") (pintype "passive"))
      (node (ref "T6") (pin "5") (pinfunction "G_5") (pintype "passive"))
    )
    (net (code "18") (name "D15_SDA") (class "Default")
      (node (ref "IC2") (pin "13") (pinfunction "(SDA/S0:0|2:0/T0:0|1:2/AIN16)PA08_13") (pintype "bidirectional"))
      (node (ref "R39") (pin "1") (pinfunction "1_1") (pintype "passive"))
      (node (ref "T6") (pin "4") (pinfunction "S_4") (pintype "passive"))
    )
    (net (code "19") (name "D16_SCL") (class "Default")
      (node (ref "IC2") (pin "14") (pinfunction "(SCL/S0:1|2:1/T0:1|1:3/AIN17)PA09_14") (pintype "bidirectional"))
      (node (ref "R38") (pin "1") (pinfunction "1_1") (pintype "passive"))
      (node (ref "T6") (pin "1") (pinfunction "S_1") (pintype "passive"))
    )
    (net (code "20") (name "D17_SDA_IMU") (class "Default")
      (node (ref "IC2") (pin "21") (pinfunction "(SDA/S2:0|4:0/T2:0|0:6)PA12_21") (pintype "bidirectional"))
      (node (ref "IC6") (pin "11") (pinfunction "SDX_11") (pintype "bidirectional"))
      (node (ref "IC7") (pin "5") (pinfunction "SDA_5") (pintype "bidirectional"))
      (node (ref "R45") (pin "1") (pinfunction "1_1") (pintype "passive"))
    )
    (net (code "21") (name "D18_SCL_IMU") (class "Default")
      (node (ref "IC2") (pin "22") (pinfunction "(SCL/S2:1|4:1/T2:1|0:7)PA13_22") (pintype "bidirectional"))
      (node (ref "IC6") (pin "9") (pinfunction "SCX_9") (pintype "bidirectional"))
      (node (ref "IC7") (pin "6") (pinfunction "SCL_6") (pintype "bidirectional"))
      (node (ref "R44") (pin "1") (pinfunction "1_1") (pintype "passive"))
    )
    (net (code "22") (name "D19_MOSI") (class "Default")
      (node (ref "IC2") (pin "25") (pinfunction "(SDA/S1:0|3:0/T2:0|0:6)PA16_25") (pintype "bidirectional"))
      (node (ref "IC5") (pin "13") (pinfunction "A2_13") (pintype "input"))
      (node (ref "IC5") (pin "4") (pinfunction "A2_4") (pintype "input"))
    )
    (net (code "23") (name "D20_SCK") (class "Default")
      (node (ref "IC2") (pin "26") (pinfunction "(SCL/S1:1|3:1/T2:1|0:7)PA17_26") (pintype "bidirectional"))
      (node (ref "IC5") (pin "15") (pinfunction "A3_15") (pintype "input"))
      (node (ref "IC5") (pin "6") (pinfunction "A3_6") (pintype "input"))
    )
    (net (code "24") (name "D21_MISO") (class "Default")
      (node (ref "IC2") (pin "28") (pinfunction "(S1:3|3:3/T3:1|0:3)PA19_28") (pintype "bidirectional"))
      (node (ref "IC5") (pin "12") (pinfunction "Y4_12") (pintype "tri_state"))
      (node (ref "IC5") (pin "9") (pinfunction "Y1_9") (pintype "tri_state"))
    )
    (net (code "25") (name "D22_~{XB1_PWR}") (class "Default")
      (node (ref "IC2") (pin "48") (pinfunction "(S:1/T6:1/AIN11)PB03_48") (pintype "bidirectional"))
      (node (ref "R18") (pin "2") (pinfunction "2_2") (pintype "passive"))
      (node (ref "T2") (pin "1") (pinfunction "G_1") (pintype "passive"))
    )
    (net (code "26") (name "D23_CS_XB1") (class "Default")
      (node (ref "IC2") (pin "27") (pinfunction "(S1:2|3:2/T3:0|0:2)PA18_27") (pintype "bidirectional"))
      (node (ref "T1") (pin "1") (pinfunction "S_1") (pintype "passive"))
    )
    (net (code "27") (name "D24_INT_XB1") (class "Default")
      (node (ref "IC2") (pin "30") (pinfunction "(S5:3|3:3/T7:1|0:7)PA21_30") (pintype "bidirectional"))
      (node (ref "R15") (pin "2") (pinfunction "2_2") (pintype "passive"))
    )
    (net (code "28") (name "D25_TX_XB1") (class "Default")
      (node (ref "IC2") (pin "37") (pinfunction "(S5:2/T7:0)PB22_37") (pintype "bidirectional"))
      (node (ref "R8") (pin "1") (pinfunction "1_1") (pintype "passive"))
    )
    (net (code "29") (name "D26_RX_XB1") (class "Default")
      (node (ref "IC2") (pin "38") (pinfunction "(S5:3/T7:1)PB23_38") (pintype "bidirectional"))
      (node (ref "R10") (pin "1") (pinfunction "1_1") (pintype "passive"))
    )
    (net (code "30") (name "D27_~{XB2_PWR}") (class "Default")
      (node (ref "IC2") (pin "19") (pinfunction "(S4:2/T5:0|0:4)PB10_19") (pintype "bidirectional"))
      (node (ref "R20") (pin "2") (pinfunction "2_2") (pintype "passive"))
      (node (ref "T3") (pin "1") (pinfunction "G_1") (pintype "passive"))
    )
    (net (code "31") (name "D28_CS_XB2") (class "Default")
      (node (ref "IC2") (pin "23") (pinfunction "(XIN/S2:2|4:2/T3:0|0:4)PA14_23") (pintype "bidirectional"))
      (node (ref "T1") (pin "4") (pinfunction "S_4") (pintype "passive"))
    )
    (net (code "32") (name "D29_INT_XB2") (class "Default")
      (node (ref "IC2") (pin "24") (pinfunction "(XOUT/S2:3|4:3/T3:1|0:5)PA15_24") (pintype "bidirectional"))
      (node (ref "R17") (pin "2") (pinfunction "2_2") (pintype "passive"))
    )
    (net (code "33") (name "D30_TX_XB2") (class "Default")
      (node (ref "IC2") (pin "15") (pinfunction "(S0:2|2:2/T1:0|0:2/AIN18)PA10_15") (pintype "bidirectional"))
      (node (ref "R9") (pin "1") (pinfunction "1_1") (pintype "passive"))
    )
    (net (code "34") (name "D31_RX_XB2") (class "Default")
      (node (ref "IC2") (pin "16") (pinfunction "(S0:3|2:3/T1:1|0:3/AIN19)PA11_16") (pintype "bidirectional"))
      (node (ref "R11") (pin "1") (pinfunction "1_1") (pintype "passive"))
    )
    (net (code "35") (name "GND") (class "Default")
      (node (ref "C1") (pin "1") (pinfunction "1_1") (pintype "passive"))
      (node (ref "C10") (pin "1") (pinfunction "1_1") (pintype "passive"))
      (node (ref "C11") (pin "1") (pinfunction "1_1") (pintype "passive"))
      (node (ref "C12") (pin "1") (pinfunction "1_1") (pintype "passive"))
      (node (ref "C13") (pin "1") (pinfunction "1_1") (pintype "passive"))
      (node (ref "C14") (pin "2") (pinfunction "2_2") (pintype "passive"))
      (node (ref "C15") (pin "1") (pinfunction "1_1") (pintype "passive"))
      (node (ref "C16") (pin "1") (pinfunction "1_1") (pintype "passive"))
      (node (ref "C17") (pin "1") (pinfunction "1_1") (pintype "passive"))
      (node (ref "C18") (pin "1") (pinfunction "1_1") (pintype "passive"))
      (node (ref "C19") (pin "1") (pinfunction "1_1") (pintype "passive"))
      (node (ref "C2") (pin "1") (pinfunction "1_1") (pintype "passive"))
      (node (ref "C20") (pin "1") (pinfunction "1_1") (pintype "passive"))
      (node (ref "C21") (pin "1") (pinfunction "1_1") (pintype "passive"))
      (node (ref "C22") (pin "1") (pinfunction "1_1") (pintype "passive"))
      (node (ref "C23") (pin "1") (pinfunction "1_1") (pintype "passive"))
      (node (ref "C24") (pin "1") (pinfunction "1_1") (pintype "passive"))
      (node (ref "C25") (pin "1") (pinfunction "1_1") (pintype "passive"))
      (node (ref "C26") (pin "1") (pinfunction "1_1") (pintype "passive"))
      (node (ref "C27") (pin "1") (pinfunction "1_1") (pintype "passive"))
      (node (ref "C3") (pin "1") (pinfunction "1_1") (pintype "passive"))
      (node (ref "C4") (pin "1") (pinfunction "1_1") (pintype "passive"))
      (node (ref "C5") (pin "1") (pinfunction "1_1") (pintype "passive"))
      (node (ref "C6") (pin "1") (pinfunction "1_1") (pintype "passive"))
      (node (ref "C7") (pin "1") (pinfunction "1_1") (pintype "passive"))
      (node (ref "C8") (pin "1") (pinfunction "1_1") (pintype "passive"))
      (node (ref "C9") (pin "1") (pinfunction "1_1") (pintype "passive"))
      (node (ref "D10") (pin "1") (pinfunction "A_1") (pintype "passive"))
      (node (ref "D11") (pin "1") (pinfunction "A_1") (pintype "passive"))
      (node (ref "D12") (pin "1") (pinfunction "A_1") (pintype "passive"))
      (node (ref "D13") (pin "1") (pinfunction "A_1") (pintype "passive"))
      (node (ref "D14") (pin "1") (pinfunction "A_1") (pintype "passive"))
      (node (ref "D15") (pin "1") (pinfunction "A_1") (pintype "passive"))
      (node (ref "D16") (pin "C") (pinfunction "C_C") (pintype "passive"))
      (node (ref "D17") (pin "1") (pinfunction "A_1") (pintype "passive"))
      (node (ref "D18") (pin "1") (pinfunction "A_1") (pintype "passive"))
      (node (ref "D19") (pin "1") (pinfunction "A_1") (pintype "passive"))
      (node (ref "D2") (pin "C") (pinfunction "C_C") (pintype "passive"))
      (node (ref "D20") (pin "C") (pinfunction "C_C") (pintype "passive"))
      (node (ref "D3") (pin "C") (pinfunction "C_C") (pintype "passive"))
      (node (ref "D4") (pin "A") (pinfunction "A_A") (pintype "passive"))
      (node (ref "D5") (pin "3") (pinfunction "A_3") (pintype "passive"))
      (node (ref "D6") (pin "A") (pinfunction "A_A") (pintype "passive"))
      (node (ref "D7") (pin "C") (pinfunction "C_C") (pintype "passive"))
      (node (ref "D8") (pin "C") (pinfunction "C_C") (pintype "passive"))
      (node (ref "D9") (pin "1") (pinfunction "A_1") (pintype "passive"))
      (node (ref "IC1") (pin "1") (pinfunction "GND_1") (pintype "power_in"))
      (node (ref "IC2") (pin "18") (pinfunction "GND_18") (pintype "power_in"))
      (node (ref "IC2") (pin "35") (pinfunction "GND_35") (pintype "power_in"))
      (node (ref "IC2") (pin "42") (pinfunction "GND_42") (pintype "power_in"))
      (node (ref "IC2") (pin "5") (pinfunction "GND_5") (pintype "power_in"))
      (node (ref "IC2") (pin "TP") (pinfunction "GND_TP") (pintype "power_in"))
      (node (ref "IC3") (pin "1") (pinfunction "GND_1") (pintype "power_in"))
      (node (ref "IC4") (pin "1") (pinfunction "GND_1") (pintype "power_in"))
      (node (ref "IC5") (pin "10") (pinfunction "GND_10") (pintype "power_in"))
      (node (ref "IC6") (pin "4") (pinfunction "GNDA_4") (pintype "power_in"))
      (node (ref "IC6") (pin "6") (pinfunction "GND_6") (pintype "power_in"))
      (node (ref "IC7") (pin "4") (pinfunction "GND_4") (pintype "power_in"))
      (node (ref "J1") (pin "GND") (pinfunction "GND_GND") (pintype "power_in"))
      (node (ref "J10") (pin "1") (pinfunction "1_1") (pintype "passive"))
      (node (ref "J11") (pin "1") (pinfunction "1_1") (pintype "passive"))
      (node (ref "J12") (pin "1") (pinfunction "1_1") (pintype "passive"))
      (node (ref "J13") (pin "1") (pinfunction "1_1") (pintype "passive"))
      (node (ref "J14") (pin "1") (pinfunction "1_1") (pintype "passive"))
      (node (ref "J15") (pin "3") (pinfunction "3_3") (pintype "passive"))
      (node (ref "J2") (pin "2") (pinfunction "2_2") (pintype "passive"))
      (node (ref "J3") (pin "GND@1") (pinfunction "GND_GND@1") (pintype "power_in"))
      (node (ref "J3") (pin "GND@2") (pinfunction "GND_GND@2") (pintype "power_in"))
      (node (ref "J3") (pin "GND@3") (pinfunction "GND_GND@3") (pintype "power_in"))
      (node (ref "J4") (pin "1") (pinfunction "1_1") (pintype "passive"))
      (node (ref "J5") (pin "1") (pinfunction "1_1") (pintype "passive"))
      (node (ref "J6") (pin "1") (pinfunction "1_1") (pintype "passive"))
      (node (ref "J7") (pin "1") (pinfunction "1_1") (pintype "passive"))
      (node (ref "J8") (pin "1") (pinfunction "1_1") (pintype "passive"))
      (node (ref "J9") (pin "1") (pinfunction "1_1") (pintype "passive"))
      (node (ref "R1") (pin "1") (pinfunction "1_1") (pintype "passive"))
      (node (ref "R19") (pin "2") (pinfunction "2_2") (pintype "passive"))
      (node (ref "R21") (pin "2") (pinfunction "2_2") (pintype "passive"))
      (node (ref "R32") (pin "2") (pinfunction "2_2") (pintype "passive"))
      (node (ref "R37") (pin "2") (pinfunction "2_2") (pintype "passive"))
      (node (ref "SW1") (pin "3") (pinfunction "S1_3") (pintype "passive"))
      (node (ref "SW1") (pin "4") (pinfunction "S1_4") (pintype "passive"))
      (node (ref "SW2") (pin "1") (pinfunction "P1_1") (pintype "passive"))
      (node (ref "SW2") (pin "2") (pinfunction "P1_2") (pintype "passive"))
      (node (ref "T5") (pin "1") (pinfunction "S_1") (pintype "passive"))
      (node (ref "T5") (pin "4") (pinfunction "S_4") (pintype "passive"))
      (node (ref "XBEE1") (pin "10") (pinfunction "GND_10") (pintype "power_in"))
      (node (ref "XBEE2") (pin "10") (pinfunction "GND_10") (pintype "power_in"))
    )
    (net (code "36") (name "I2C_SCL") (class "Default")
      (node (ref "J10") (pin "4") (pinfunction "4_4") (pintype "passive"))
      (node (ref "J11") (pin "4") (pinfunction "4_4") (pintype "passive"))
      (node (ref "J12") (pin "4") (pinfunction "4_4") (pintype "passive"))
      (node (ref "J13") (pin "4") (pinfunction "4_4") (pintype "passive"))
      (node (ref "J9") (pin "4") (pinfunction "4_4") (pintype "passive"))
      (node (ref "R41") (pin "1") (pinfunction "1_1") (pintype "passive"))
      (node (ref "T6") (pin "6") (pinfunction "D_6") (pintype "passive"))
    )
    (net (code "37") (name "I2C_SDA") (class "Default")
      (node (ref "J10") (pin "3") (pinfunction "3_3") (pintype "passive"))
      (node (ref "J11") (pin "3") (pinfunction "3_3") (pintype "passive"))
      (node (ref "J12") (pin "3") (pinfunction "3_3") (pintype "passive"))
      (node (ref "J13") (pin "3") (pinfunction "3_3") (pintype "passive"))
      (node (ref "J9") (pin "3") (pinfunction "3_3") (pintype "passive"))
      (node (ref "R42") (pin "1") (pinfunction "1_1") (pintype "passive"))
      (node (ref "T6") (pin "3") (pinfunction "D_3") (pintype "passive"))
    )
    (net (code "38") (name "I2C_VCC") (class "Default")
      (node (ref "C24") (pin "2") (pinfunction "2_2") (pintype "passive"))
      (node (ref "J10") (pin "2") (pinfunction "2_2") (pintype "passive"))
      (node (ref "J11") (pin "2") (pinfunction "2_2") (pintype "passive"))
      (node (ref "J12") (pin "2") (pinfunction "2_2") (pintype "passive"))
      (node (ref "J13") (pin "2") (pinfunction "2_2") (pintype "passive"))
      (node (ref "J9") (pin "2") (pinfunction "2_2") (pintype "passive"))
      (node (ref "R41") (pin "2") (pinfunction "2_2") (pintype "passive"))
      (node (ref "R42") (pin "2") (pinfunction "2_2") (pintype "passive"))
      (node (ref "R43") (pin "2") (pinfunction "2_2") (pintype "passive"))
      (node (ref "T7") (pin "3") (pinfunction "D_3") (pintype "passive"))
    )
    (net (code "39") (name "IO1") (class "Default")
      (node (ref "J5") (pin "3") (pinfunction "3_3") (pintype "passive"))
      (node (ref "R31") (pin "2") (pinfunction "2_2") (pintype "passive"))
    )
    (net (code "40") (name "IO2") (class "Default")
      (node (ref "J5") (pin "4") (pinfunction "4_4") (pintype "passive"))
      (node (ref "R30") (pin "2") (pinfunction "2_2") (pintype "passive"))
    )
    (net (code "41") (name "IO3") (class "Default")
      (node (ref "J6") (pin "3") (pinfunction "3_3") (pintype "passive"))
      (node (ref "R29") (pin "2") (pinfunction "2_2") (pintype "passive"))
    )
    (net (code "42") (name "IO4") (class "Default")
      (node (ref "J6") (pin "4") (pinfunction "4_4") (pintype "passive"))
      (node (ref "R28") (pin "2") (pinfunction "2_2") (pintype "passive"))
    )
    (net (code "43") (name "IO5") (class "Default")
      (node (ref "J8") (pin "3") (pinfunction "3_3") (pintype "passive"))
      (node (ref "R27") (pin "2") (pinfunction "2_2") (pintype "passive"))
    )
    (net (code "44") (name "IO6") (class "Default")
      (node (ref "J8") (pin "4") (pinfunction "4_4") (pintype "passive"))
      (node (ref "R26") (pin "2") (pinfunction "2_2") (pintype "passive"))
    )
    (net (code "45") (name "Net-(D1-PadA)") (class "Default")
      (node (ref "D1") (pin "A") (pinfunction "A_A") (pintype "passive"))
      (node (ref "J2") (pin "1") (pinfunction "1_1") (pintype "passive"))
    )
    (net (code "46") (name "Net-(D1-PadC)") (class "Default")
      (node (ref "D1") (pin "C") (pinfunction "C_C") (pintype "passive"))
      (node (ref "F2") (pin "1") (pinfunction "1_1") (pintype "passive"))
    )
    (net (code "47") (name "Net-(D2-PadA)") (class "Default")
      (node (ref "D2") (pin "A") (pinfunction "A_A") (pintype "passive"))
      (node (ref "R3") (pin "2") (pinfunction "2_2") (pintype "passive"))
    )
    (net (code "48") (name "Net-(D3-PadA)") (class "Default")
      (node (ref "D3") (pin "A") (pinfunction "A_A") (pintype "passive"))
      (node (ref "R4") (pin "2") (pinfunction "2_2") (pintype "passive"))
    )
    (net (code "49") (name "Net-(D7-PadA)") (class "Default")
      (node (ref "D7") (pin "A") (pinfunction "A_A") (pintype "passive"))
      (node (ref "R22") (pin "1") (pinfunction "1_1") (pintype "passive"))
    )
    (net (code "50") (name "Net-(D8-PadA)") (class "Default")
      (node (ref "D8") (pin "A") (pinfunction "A_A") (pintype "passive"))
      (node (ref "R23") (pin "1") (pinfunction "1_1") (pintype "passive"))
    )
    (net (code "51") (name "Net-(D16-PadA)") (class "Default")
      (node (ref "D16") (pin "A") (pinfunction "A_A") (pintype "passive"))
      (node (ref "R34") (pin "1") (pinfunction "1_1") (pintype "passive"))
    )
    (net (code "52") (name "Net-(D20-PadA)") (class "Default")
      (node (ref "D20") (pin "A") (pinfunction "A_A") (pintype "passive"))
      (node (ref "R43") (pin "1") (pinfunction "1_1") (pintype "passive"))
    )
    (net (code "53") (name "Net-(F1-Pad1)") (class "Default")
      (node (ref "F1") (pin "1") (pinfunction "1_1") (pintype "passive"))
      (node (ref "J1") (pin "VBUS") (pinfunction "VBUS_VBUS") (pintype "power_in"))
    )
    (net (code "54") (name "Net-(IC2-(XIN32{slash}S1:0{slash}T2:0)PA00)") (class "Default")
      (node (ref "C14") (pin "1") (pinfunction "1_1") (pintype "passive"))
      (node (ref "IC2") (pin "1") (pinfunction "(XIN32/S1:0/T2:0)PA00_1") (pintype "bidirectional"))
      (node (ref "Q1") (pin "2") (pinfunction "2_2") (pintype "passive"))
    )
    (net (code "55") (name "Net-(IC2-(XOUT32{slash}S1:1{slash}T2:1)PA01)") (class "Default")
      (node (ref "C15") (pin "2") (pinfunction "2_2") (pintype "passive"))
      (node (ref "IC2") (pin "2") (pinfunction "(XOUT32/S1:1/T2:1)PA01_2") (pintype "bidirectional"))
      (node (ref "Q1") (pin "1") (pinfunction "1_1") (pintype "passive"))
    )
    (net (code "56") (name "Net-(IC2-VCCANA)") (class "Default")
      (node (ref "C10") (pin "2") (pinfunction "2_2") (pintype "passive"))
      (node (ref "C11") (pin "2") (pinfunction "2_2") (pintype "passive"))
      (node (ref "C8") (pin "2") (pinfunction "2_2") (pintype "passive"))
      (node (ref "IC2") (pin "6") (pinfunction "VCCANA_6") (pintype "power_in"))
      (node (ref "L1") (pin "2") (pinfunction "2_2") (pintype "passive"))
    )
    (net (code "57") (name "Net-(IC2-VCCCORE)") (class "Default")
      (node (ref "C13") (pin "2") (pinfunction "2_2") (pintype "passive"))
      (node (ref "IC2") (pin "43") (pinfunction "VCCCORE_43") (pintype "power_in"))
    )
    (net (code "58") (name "Net-(IC3-RST)") (class "Default")
      (node (ref "IC3") (pin "2") (pinfunction "RST_2") (pintype "output"))
      (node (ref "XBEE2") (pin "5") (pinfunction "~{RESET}_5") (pintype "bidirectional"))
    )
    (net (code "59") (name "Net-(IC4-RST)") (class "Default")
      (node (ref "IC4") (pin "2") (pinfunction "RST_2") (pintype "output"))
      (node (ref "XBEE1") (pin "5") (pinfunction "~{RESET}_5") (pintype "bidirectional"))
    )
    (net (code "60") (name "Net-(IC5A-A1)") (class "Default")
      (node (ref "IC5") (pin "1") (pinfunction "G_1") (pintype "input"))
      (node (ref "IC5") (pin "2") (pinfunction "A1_2") (pintype "input"))
      (node (ref "R12") (pin "1") (pinfunction "1_1") (pintype "passive"))
      (node (ref "T1") (pin "6") (pinfunction "D_6") (pintype "passive"))
    )
    (net (code "61") (name "Net-(IC5B-A4)") (class "Default")
      (node (ref "IC5") (pin "17") (pinfunction "A4_17") (pintype "input"))
      (node (ref "IC5") (pin "19") (pinfunction "G_19") (pintype "input"))
      (node (ref "R13") (pin "1") (pinfunction "1_1") (pintype "passive"))
      (node (ref "T1") (pin "3") (pinfunction "D_3") (pintype "passive"))
    )
    (net (code "62") (name "Net-(IC6-SDO1)") (class "Default")
      (node (ref "IC6") (pin "17") (pinfunction "SDO1_17") (pintype "bidirectional"))
      (node (ref "J15") (pin "2") (pinfunction "2_2") (pintype "passive"))
    )
    (net (code "63") (name "Net-(IC6-SDO2)") (class "Default")
      (node (ref "IC6") (pin "12") (pinfunction "SDO2_12") (pintype "bidirectional"))
      (node (ref "J14") (pin "2") (pinfunction "2_2") (pintype "passive"))
    )
    (net (code "64") (name "Net-(J1-SHIELD-PadSHLD1)") (class "Default")
      (node (ref "J1") (pin "SHLD1") (pinfunction "SHIELD_SHLD1") (pintype "passive"))
      (node (ref "J1") (pin "SHLD2") (pinfunction "SHIELD_SHLD2") (pintype "passive"))
      (node (ref "J1") (pin "SHLD3") (pinfunction "SHIELD_SHLD3") (pintype "passive"))
      (node (ref "J1") (pin "SHLD4") (pinfunction "SHIELD_SHLD4") (pintype "passive"))
      (node (ref "J1") (pin "SHLD5") (pinfunction "SHIELD_SHLD5") (pintype "passive"))
      (node (ref "J1") (pin "SHLD6") (pinfunction "SHIELD_SHLD6") (pintype "passive"))
      (node (ref "J1") (pin "SHLD7") (pinfunction "SHIELD_SHLD7") (pintype "passive"))
      (node (ref "J1") (pin "SHLD8") (pinfunction "SHIELD_SHLD8") (pintype "passive"))
      (node (ref "R1") (pin "2") (pinfunction "2_2") (pintype "passive"))
    )
    (net (code "65") (name "Net-(J4-Pad3)") (class "Default")
      (node (ref "J4") (pin "3") (pinfunction "3_3") (pintype "passive"))
      (node (ref "R25") (pin "2") (pinfunction "2_2") (pintype "passive"))
    )
    (net (code "66") (name "Net-(J4-Pad4)") (class "Default")
      (node (ref "J4") (pin "4") (pinfunction "4_4") (pintype "passive"))
      (node (ref "R24") (pin "2") (pinfunction "2_2") (pintype "passive"))
    )
    (net (code "67") (name "Net-(J7-Pad3)") (class "Default")
      (node (ref "J7") (pin "3") (pinfunction "3_3") (pintype "passive"))
      (node (ref "R36") (pin "2") (pinfunction "2_2") (pintype "passive"))
    )
    (net (code "68") (name "Net-(J7-Pad4)") (class "Default")
      (node (ref "J7") (pin "4") (pinfunction "4_4") (pintype "passive"))
      (node (ref "R35") (pin "2") (pinfunction "2_2") (pintype "passive"))
    )
    (net (code "69") (name "Net-(R2-Pad2)") (class "Default")
      (node (ref "R2") (pin "2") (pinfunction "2_2") (pintype "passive"))
      (node (ref "SW1") (pin "1") (pinfunction "P1_1") (pintype "passive"))
      (node (ref "SW1") (pin "2") (pinfunction "P1_2") (pintype "passive"))
    )
    (net (code "70") (name "Net-(R6-Pad2)") (class "Default")
      (node (ref "R6") (pin "2") (pinfunction "2_2") (pintype "passive"))
      (node (ref "SW2") (pin "3") (pinfunction "S1_3") (pintype "passive"))
      (node (ref "SW2") (pin "4") (pinfunction "S1_4") (pintype "passive"))
    )
    (net (code "71") (name "Net-(T4-G)") (class "Default")
      (node (ref "R33") (pin "2") (pinfunction "2_2") (pintype "passive"))
      (node (ref "T4") (pin "1") (pinfunction "G_1") (pintype "passive"))
      (node (ref "T5") (pin "3") (pinfunction "D_3") (pintype "passive"))
    )
    (net (code "72") (name "Net-(T5A-D)") (class "Default")
      (node (ref "R40") (pin "2") (pinfunction "2_2") (pintype "passive"))
      (node (ref "T5") (pin "6") (pinfunction "D_6") (pintype "passive"))
      (node (ref "T7") (pin "1") (pinfunction "G_1") (pintype "passive"))
    )
    (net (code "73") (name "Net-(XBEE1-DIN{slash}RX{slash}~{CFG})") (class "Default")
      (node (ref "R8") (pin "2") (pinfunction "2_2") (pintype "passive"))
      (node (ref "XBEE1") (pin "3") (pinfunction "DIN/RX/~{CFG}_3") (pintype "bidirectional"))
    )
    (net (code "74") (name "Net-(XBEE1-DIO7{slash}CTS)") (class "Default")
      (node (ref "R15") (pin "1") (pinfunction "1_1") (pintype "passive"))
      (node (ref "XBEE1") (pin "12") (pinfunction "DIO7/CTS_12") (pintype "bidirectional"))
    )
    (net (code "75") (name "Net-(XBEE1-DOUT{slash}TX)") (class "Default")
      (node (ref "R10") (pin "2") (pinfunction "2_2") (pintype "passive"))
      (node (ref "XBEE1") (pin "2") (pinfunction "DOUT/TX_2") (pintype "bidirectional"))
    )
    (net (code "76") (name "Net-(XBEE2-DIN{slash}RX{slash}~{CFG})") (class "Default")
      (node (ref "R9") (pin "2") (pinfunction "2_2") (pintype "passive"))
      (node (ref "XBEE2") (pin "3") (pinfunction "DIN/RX/~{CFG}_3") (pintype "bidirectional"))
    )
    (net (code "77") (name "Net-(XBEE2-DIO7{slash}CTS)") (class "Default")
      (node (ref "R17") (pin "1") (pinfunction "1_1") (pintype "passive"))
      (node (ref "XBEE2") (pin "12") (pinfunction "DIO7/CTS_12") (pintype "bidirectional"))
    )
    (net (code "78") (name "Net-(XBEE2-DOUT{slash}TX)") (class "Default")
      (node (ref "R11") (pin "2") (pinfunction "2_2") (pintype "passive"))
      (node (ref "XBEE2") (pin "2") (pinfunction "DOUT/TX_2") (pintype "bidirectional"))
    )
    (net (code "79") (name "RST") (class "Default")
      (node (ref "C12") (pin "2") (pinfunction "2_2") (pintype "passive"))
      (node (ref "IC2") (pin "40") (pinfunction "~{RESET}_40") (pintype "input"))
      (node (ref "J3") (pin "RST") (pinfunction "RST_RST") (pintype "bidirectional"))
      (node (ref "R6") (pin "1") (pinfunction "1_1") (pintype "passive"))
      (node (ref "R7") (pin "2") (pinfunction "2_2") (pintype "passive"))
    )
    (net (code "80") (name "SWCLK") (class "Default")
      (node (ref "IC2") (pin "45") (pinfunction "(SWCLK/S1:2/T1:0)PA30_45") (pintype "bidirectional"))
      (node (ref "J3") (pin "SWCLK") (pinfunction "SWCLK_SWCLK") (pintype "bidirectional"))
      (node (ref "R5") (pin "2") (pinfunction "2_2") (pintype "passive"))
    )
    (net (code "81") (name "SWDIO") (class "Default")
      (node (ref "IC2") (pin "46") (pinfunction "(SWDIO/S1:3/T1:1)PA31_46") (pintype "bidirectional"))
      (node (ref "J3") (pin "SWDIO") (pinfunction "SWDIO_SWDIO") (pintype "bidirectional"))
    )
    (net (code "82") (name "UART_VCC") (class "Default")
      (node (ref "C23") (pin "2") (pinfunction "2_2") (pintype "passive"))
      (node (ref "J4") (pin "2") (pinfunction "2_2") (pintype "passive"))
      (node (ref "J7") (pin "2") (pinfunction "2_2") (pintype "passive"))
      (node (ref "R34") (pin "2") (pinfunction "2_2") (pintype "passive"))
      (node (ref "T4") (pin "3") (pinfunction "D_3") (pintype "passive"))
    )
    (net (code "83") (name "USB_D_N") (class "Default")
      (node (ref "D5") (pin "1") (pinfunction "C1_1") (pintype "passive"))
      (node (ref "IC2") (pin "33") (pinfunction "(USBM/S3:2|5:2/T5:0|1:2)PA24_33") (pintype "bidirectional"))
      (node (ref "J1") (pin "D-") (pinfunction "D-_D-") (pintype "bidirectional"))
    )
    (net (code "84") (name "USB_D_P") (class "Default")
      (node (ref "D5") (pin "2") (pinfunction "C2_2") (pintype "passive"))
      (node (ref "IC2") (pin "34") (pinfunction "(USBP/S3:3|5:3/T5:1|1:3)PA25_34") (pintype "bidirectional"))
      (node (ref "J1") (pin "D+") (pinfunction "D+_D+") (pintype "bidirectional"))
    )
    (net (code "85") (name "XB1_CS") (class "Default")
      (node (ref "IC5") (pin "18") (pinfunction "Y1_18") (pintype "tri_state"))
      (node (ref "R14") (pin "1") (pinfunction "1_1") (pintype "passive"))
      (node (ref "XBEE1") (pin "17") (pinfunction "AD3/DIO3/SS_17") (pintype "bidirectional"))
    )
    (net (code "86") (name "XB1_MISO") (class "Default")
      (node (ref "IC5") (pin "8") (pinfunction "A4_8") (pintype "input"))
      (node (ref "XBEE1") (pin "4") (pinfunction "MISO/DIO12_4") (pintype "bidirectional"))
    )
    (net (code "87") (name "XB1_MOSI") (class "Default")
      (node (ref "IC5") (pin "16") (pinfunction "Y2_16") (pintype "tri_state"))
      (node (ref "XBEE1") (pin "11") (pinfunction "DIO4/MOSI_11") (pintype "bidirectional"))
    )
    (net (code "88") (name "XB1_SCK") (class "Default")
      (node (ref "IC5") (pin "14") (pinfunction "Y3_14") (pintype "tri_state"))
      (node (ref "XBEE1") (pin "18") (pinfunction "AD2/DIO2/SCK_18") (pintype "bidirectional"))
    )
    (net (code "89") (name "XB1_VCC") (class "Default")
      (node (ref "C16") (pin "2") (pinfunction "2_2") (pintype "passive"))
      (node (ref "C18") (pin "2") (pinfunction "2_2") (pintype "passive"))
      (node (ref "C20") (pin "2") (pinfunction "2_2") (pintype "passive"))
      (node (ref "IC4") (pin "3") (pinfunction "VCC_3") (pintype "power_in"))
      (node (ref "R14") (pin "2") (pinfunction "2_2") (pintype "passive"))
      (node (ref "R19") (pin "1") (pinfunction "1_1") (pintype "passive"))
      (node (ref "R22") (pin "2") (pinfunction "2_2") (pintype "passive"))
      (node (ref "T1") (pin "2") (pinfunction "G_2") (pintype "passive"))
      (node (ref "T2") (pin "3") (pinfunction "D_3") (pintype "passive"))
      (node (ref "XBEE1") (pin "1") (pinfunction "VCC_1") (pintype "power_in"))
    )
    (net (code "90") (name "XB2_CS") (class "Default")
      (node (ref "IC5") (pin "3") (pinfunction "Y4_3") (pintype "tri_state"))
      (node (ref "R16") (pin "1") (pinfunction "1_1") (pintype "passive"))
      (node (ref "XBEE2") (pin "17") (pinfunction "AD3/DIO3/SS_17") (pintype "bidirectional"))
    )
    (net (code "91") (name "XB2_MISO") (class "Default")
      (node (ref "IC5") (pin "11") (pinfunction "A1_11") (pintype "input"))
      (node (ref "XBEE2") (pin "4") (pinfunction "MISO/DIO12_4") (pintype "bidirectional"))
    )
    (net (code "92") (name "XB2_MOSI") (class "Default")
      (node (ref "IC5") (pin "7") (pinfunction "Y2_7") (pintype "tri_state"))
      (node (ref "XBEE2") (pin "11") (pinfunction "DIO4/MOSI_11") (pintype "bidirectional"))
    )
    (net (code "93") (name "XB2_SCK") (class "Default")
      (node (ref "IC5") (pin "5") (pinfunction "Y3_5") (pintype "tri_state"))
      (node (ref "XBEE2") (pin "18") (pinfunction "AD2/DIO2/SCK_18") (pintype "bidirectional"))
    )
    (net (code "94") (name "XB2_VCC") (class "Default")
      (node (ref "C17") (pin "2") (pinfunction "2_2") (pintype "passive"))
      (node (ref "C19") (pin "2") (pinfunction "2_2") (pintype "passive"))
      (node (ref "C21") (pin "2") (pinfunction "2_2") (pintype "passive"))
      (node (ref "IC3") (pin "3") (pinfunction "VCC_3") (pintype "power_in"))
      (node (ref "R16") (pin "2") (pinfunction "2_2") (pintype "passive"))
      (node (ref "R21") (pin "1") (pinfunction "1_1") (pintype "passive"))
      (node (ref "R23") (pin "2") (pinfunction "2_2") (pintype "passive"))
      (node (ref "T1") (pin "5") (pinfunction "G_5") (pintype "passive"))
      (node (ref "T3") (pin "3") (pinfunction "D_3") (pintype "passive"))
      (node (ref "XBEE2") (pin "1") (pinfunction "VCC_1") (pintype "power_in"))
    )
    (net (code "95") (name "unconnected-(IC6-CSB1-Pad16)") (class "Default")
      (node (ref "IC6") (pin "16") (pinfunction "CSB1_16") (pintype "bidirectional"))
    )
    (net (code "96") (name "unconnected-(IC6-CSB2-Pad5)") (class "Default")
      (node (ref "IC6") (pin "5") (pinfunction "CSB2_5") (pintype "bidirectional"))
    )
    (net (code "97") (name "unconnected-(IC6-CSB3-Pad20)") (class "Default")
      (node (ref "IC6") (pin "20") (pinfunction "CSB3_20") (pintype "bidirectional"))
    )
    (net (code "98") (name "unconnected-(IC6-DRDYM-Pad2)") (class "Default")
      (node (ref "IC6") (pin "2") (pinfunction "DRDYM_2") (pintype "bidirectional"))
    )
    (net (code "99") (name "unconnected-(IC6-INT1-Pad19)") (class "Default")
      (node (ref "IC6") (pin "19") (pinfunction "INT1_19") (pintype "output"))
    )
    (net (code "100") (name "unconnected-(IC6-INT2-Pad1)") (class "Default")
      (node (ref "IC6") (pin "1") (pinfunction "INT2_1") (pintype "output"))
    )
    (net (code "101") (name "unconnected-(IC6-INT3-Pad14)") (class "Default")
      (node (ref "IC6") (pin "14") (pinfunction "INT3_14") (pintype "output"))
    )
    (net (code "102") (name "unconnected-(IC6-INT4-Pad15)") (class "Default")
      (node (ref "IC6") (pin "15") (pinfunction "INT4_15") (pintype "output"))
    )
    (net (code "103") (name "unconnected-(IC6-INT5-Pad10)") (class "Default")
      (node (ref "IC6") (pin "10") (pinfunction "INT5_10") (pintype "bidirectional"))
    )
    (net (code "104") (name "unconnected-(XBEE1-AD0{slash}DIO0{slash}SDA{slash}CB-Pad20)") (class "Default")
      (node (ref "XBEE1") (pin "20") (pinfunction "AD0/DIO0/SDA/CB_20") (pintype "bidirectional"))
    )
    (net (code "105") (name "unconnected-(XBEE1-AD1{slash}DIO1{slash}SCL{slash}ATTN-Pad19)") (class "Default")
      (node (ref "XBEE1") (pin "19") (pinfunction "AD1/DIO1/SCL/ATTN_19") (pintype "bidirectional"))
    )
    (net (code "106") (name "unconnected-(XBEE1-DIO5{slash}ASSC-Pad15)") (class "Default")
      (node (ref "XBEE1") (pin "15") (pinfunction "DIO5/ASSC_15") (pintype "bidirectional"))
    )
    (net (code "107") (name "unconnected-(XBEE1-DIO6{slash}RTS-Pad16)") (class "Default")
      (node (ref "XBEE1") (pin "16") (pinfunction "DIO6/RTS_16") (pintype "bidirectional"))
    )
    (net (code "108") (name "unconnected-(XBEE1-DIO9{slash}ON_~{SLEEP}-Pad13)") (class "Default")
      (node (ref "XBEE1") (pin "13") (pinfunction "DIO9/ON_~{SLEEP}_13") (pintype "bidirectional"))
    )
    (net (code "109") (name "unconnected-(XBEE1-DTR{slash}DIO8-Pad9)") (class "Default")
      (node (ref "XBEE1") (pin "9") (pinfunction "DTR/DIO8_9") (pintype "bidirectional"))
    )
    (net (code "110") (name "unconnected-(XBEE1-PWM1{slash}DIO11-Pad7)") (class "Default")
      (node (ref "XBEE1") (pin "7") (pinfunction "PWM1/DIO11_7") (pintype "bidirectional"))
    )
    (net (code "111") (name "unconnected-(XBEE1-RES-Pad8)") (class "Default")
      (node (ref "XBEE1") (pin "8") (pinfunction "RES_8") (pintype "bidirectional"))
    )
    (net (code "112") (name "unconnected-(XBEE1-RSSI{slash}PWM0{slash}DIO10-Pad6)") (class "Default")
      (node (ref "XBEE1") (pin "6") (pinfunction "RSSI/PWM0/DIO10_6") (pintype "bidirectional"))
    )
    (net (code "113") (name "unconnected-(XBEE1-VREF-Pad14)") (class "Default")
      (node (ref "XBEE1") (pin "14") (pinfunction "VREF_14") (pintype "bidirectional"))
    )
    (net (code "114") (name "unconnected-(XBEE2-AD0{slash}DIO0{slash}SDA{slash}CB-Pad20)") (class "Default")
      (node (ref "XBEE2") (pin "20") (pinfunction "AD0/DIO0/SDA/CB_20") (pintype "bidirectional"))
    )
    (net (code "115") (name "unconnected-(XBEE2-AD1{slash}DIO1{slash}SCL{slash}ATTN-Pad19)") (class "Default")
      (node (ref "XBEE2") (pin "19") (pinfunction "AD1/DIO1/SCL/ATTN_19") (pintype "bidirectional"))
    )
    (net (code "116") (name "unconnected-(XBEE2-DIO5{slash}ASSC-Pad15)") (class "Default")
      (node (ref "XBEE2") (pin "15") (pinfunction "DIO5/ASSC_15") (pintype "bidirectional"))
    )
    (net (code "117") (name "unconnected-(XBEE2-DIO6{slash}RTS-Pad16)") (class "Default")
      (node (ref "XBEE2") (pin "16") (pinfunction "DIO6/RTS_16") (pintype "bidirectional"))
    )
    (net (code "118") (name "unconnected-(XBEE2-DIO9{slash}ON_~{SLEEP}-Pad13)") (class "Default")
      (node (ref "XBEE2") (pin "13") (pinfunction "DIO9/ON_~{SLEEP}_13") (pintype "bidirectional"))
    )
    (net (code "119") (name "unconnected-(XBEE2-DTR{slash}DIO8-Pad9)") (class "Default")
      (node (ref "XBEE2") (pin "9") (pinfunction "DTR/DIO8_9") (pintype "bidirectional"))
    )
    (net (code "120") (name "unconnected-(XBEE2-PWM1{slash}DIO11-Pad7)") (class "Default")
      (node (ref "XBEE2") (pin "7") (pinfunction "PWM1/DIO11_7") (pintype "bidirectional"))
    )
    (net (code "121") (name "unconnected-(XBEE2-RES-Pad8)") (class "Default")
      (node (ref "XBEE2") (pin "8") (pinfunction "RES_8") (pintype "bidirectional"))
    )
    (net (code "122") (name "unconnected-(XBEE2-RSSI{slash}PWM0{slash}DIO10-Pad6)") (class "Default")
      (node (ref "XBEE2") (pin "6") (pinfunction "RSSI/PWM0/DIO10_6") (pintype "bidirectional"))
    )
    (net (code "123") (name "unconnected-(XBEE2-VREF-Pad14)") (class "Default")
      (node (ref "XBEE2") (pin "14") (pinfunction "VREF_14") (pintype "bidirectional"))
    )
  )
)
